# Encoders.net
KiCad netlist of a schematic drawn in Altium Designer
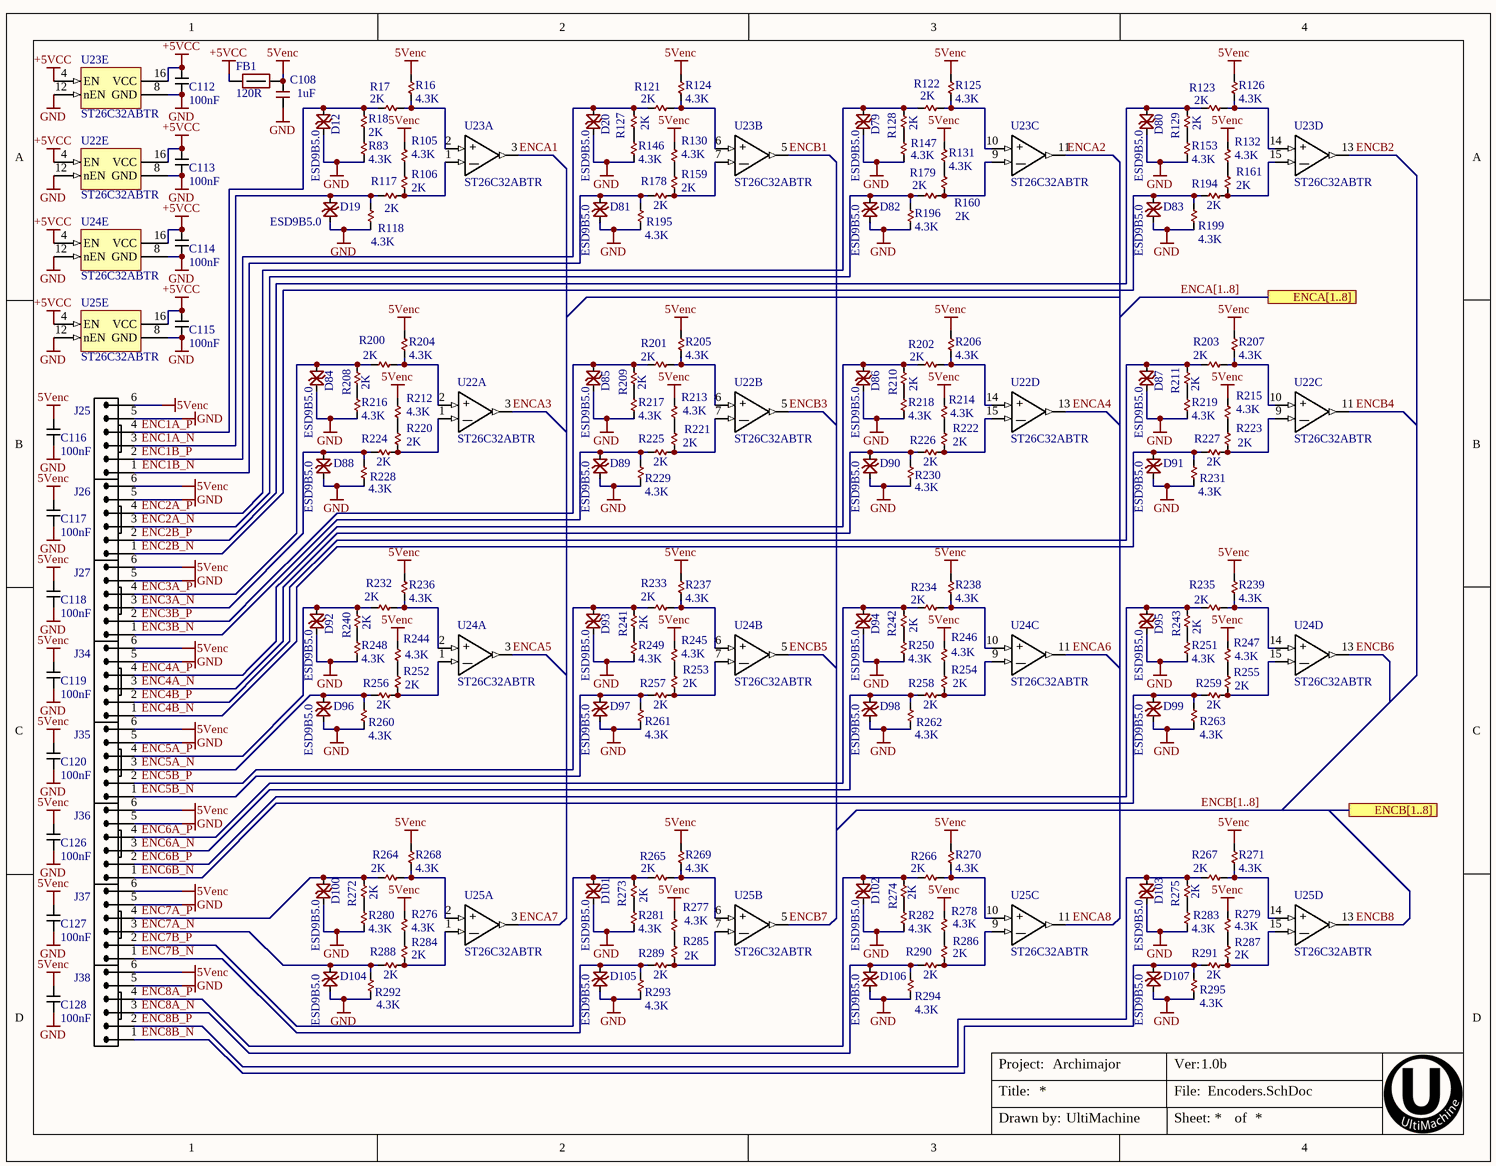
[diagram p0: Encoders.SchDoc]

(export (version "E")
  (design (tool "Eeschema 10.0.6"))
  (components
    (comp (ref "C108")
      (value "1uF")
      (footprint "C0402")
      (description "CAP CER 0402 1uF 6.3V 10% X5R")
      (fields (field (name "MANUFACTURER") "Murata") (field (name "PART") "1uF 6.3V X5R 0402"))
      (libsource (lib "Capacitors") (part "1uF 0402 6.3V X5R"))
    )
    (comp (ref "C112")
      (value "100nF")
      (footprint "C0201 Large Pads")
      (description "CAP CER 0.1UF 6.3V 10% X5R 0201")
      (fields (field (name "MANUFACTURER") "Samsung") (field (name "TOLERANCE") "10%"))
      (libsource (lib "Capacitors") (part "100nF 6.3V X5R 0201"))
    )
    (comp (ref "C113")
      (value "100nF")
      (footprint "C0201 Large Pads")
      (description "CAP CER 0.1UF 6.3V 10% X5R 0201")
      (fields (field (name "MANUFACTURER") "Samsung") (field (name "TOLERANCE") "10%"))
      (libsource (lib "Capacitors") (part "100nF 6.3V X5R 0201"))
    )
    (comp (ref "C114")
      (value "100nF")
      (footprint "C0201 Large Pads")
      (description "CAP CER 0.1UF 6.3V 10% X5R 0201")
      (fields (field (name "MANUFACTURER") "Samsung") (field (name "TOLERANCE") "10%"))
      (libsource (lib "Capacitors") (part "100nF 6.3V X5R 0201"))
    )
    (comp (ref "C115")
      (value "100nF")
      (footprint "C0201 Large Pads")
      (description "CAP CER 0.1UF 6.3V 10% X5R 0201")
      (fields (field (name "MANUFACTURER") "Samsung") (field (name "TOLERANCE") "10%"))
      (libsource (lib "Capacitors") (part "100nF 6.3V X5R 0201"))
    )
    (comp (ref "C116")
      (value "100nF")
      (footprint "C0201 Large Pads")
      (description "CAP CER 0.1UF 6.3V 10% X5R 0201")
      (fields (field (name "MANUFACTURER") "Samsung") (field (name "TOLERANCE") "10%"))
      (libsource (lib "Capacitors") (part "100nF 6.3V X5R 0201"))
    )
    (comp (ref "C117")
      (value "100nF")
      (footprint "C0201 Large Pads")
      (description "CAP CER 0.1UF 6.3V 10% X5R 0201")
      (fields (field (name "MANUFACTURER") "Samsung") (field (name "TOLERANCE") "10%"))
      (libsource (lib "Capacitors") (part "100nF 6.3V X5R 0201"))
    )
    (comp (ref "C118")
      (value "100nF")
      (footprint "C0201 Large Pads")
      (description "CAP CER 0.1UF 6.3V 10% X5R 0201")
      (fields (field (name "MANUFACTURER") "Samsung") (field (name "TOLERANCE") "10%"))
      (libsource (lib "Capacitors") (part "100nF 6.3V X5R 0201"))
    )
    (comp (ref "C119")
      (value "100nF")
      (footprint "C0201 Large Pads")
      (description "CAP CER 0.1UF 6.3V 10% X5R 0201")
      (fields (field (name "MANUFACTURER") "Samsung") (field (name "TOLERANCE") "10%"))
      (libsource (lib "Capacitors") (part "100nF 6.3V X5R 0201"))
    )
    (comp (ref "C120")
      (value "100nF")
      (footprint "C0201 Large Pads")
      (description "CAP CER 0.1UF 6.3V 10% X5R 0201")
      (fields (field (name "MANUFACTURER") "Samsung") (field (name "TOLERANCE") "10%"))
      (libsource (lib "Capacitors") (part "100nF 6.3V X5R 0201"))
    )
    (comp (ref "C126")
      (value "100nF")
      (footprint "C0201 Large Pads")
      (description "CAP CER 0.1UF 6.3V 10% X5R 0201")
      (fields (field (name "MANUFACTURER") "Samsung") (field (name "TOLERANCE") "10%"))
      (libsource (lib "Capacitors") (part "100nF 6.3V X5R 0201"))
    )
    (comp (ref "C127")
      (value "100nF")
      (footprint "C0201 Large Pads")
      (description "CAP CER 0.1UF 6.3V 10% X5R 0201")
      (fields (field (name "MANUFACTURER") "Samsung") (field (name "TOLERANCE") "10%"))
      (libsource (lib "Capacitors") (part "100nF 6.3V X5R 0201"))
    )
    (comp (ref "C128")
      (value "100nF")
      (footprint "C0201 Large Pads")
      (description "CAP CER 0.1UF 6.3V 10% X5R 0201")
      (fields (field (name "MANUFACTURER") "Samsung") (field (name "TOLERANCE") "10%"))
      (libsource (lib "Capacitors") (part "100nF 6.3V X5R 0201"))
    )
    (comp (ref "D12")
      (value "ESD9B5.0")
      (footprint "SOD923-D")
      (description "TVS DIODE BIDIR 5VWM SOD923")
      (fields (field (name "MANUFACTURER") "On Semi") (field (name "TOLERANCE") "-NA-"))
      (libsource (lib "Diodes") (part "ESD9B5.0ST5G"))
    )
    (comp (ref "D19")
      (value "ESD9B5.0")
      (footprint "SOD923-D")
      (description "TVS DIODE BIDIR 5VWM SOD923")
      (fields (field (name "MANUFACTURER") "On Semi") (field (name "TOLERANCE") "-NA-"))
      (libsource (lib "Diodes") (part "ESD9B5.0ST5G"))
    )
    (comp (ref "D20")
      (value "ESD9B5.0")
      (footprint "SOD923-D")
      (description "TVS DIODE BIDIR 5VWM SOD923")
      (fields (field (name "MANUFACTURER") "On Semi") (field (name "TOLERANCE") "-NA-"))
      (libsource (lib "Diodes") (part "ESD9B5.0ST5G"))
    )
    (comp (ref "D79")
      (value "ESD9B5.0")
      (footprint "SOD923-D")
      (description "TVS DIODE BIDIR 5VWM SOD923")
      (fields (field (name "MANUFACTURER") "On Semi") (field (name "TOLERANCE") "-NA-"))
      (libsource (lib "Diodes") (part "ESD9B5.0ST5G"))
    )
    (comp (ref "D80")
      (value "ESD9B5.0")
      (footprint "SOD923-D")
      (description "TVS DIODE BIDIR 5VWM SOD923")
      (fields (field (name "MANUFACTURER") "On Semi") (field (name "TOLERANCE") "-NA-"))
      (libsource (lib "Diodes") (part "ESD9B5.0ST5G"))
    )
    (comp (ref "D81")
      (value "ESD9B5.0")
      (footprint "SOD923-D")
      (description "TVS DIODE BIDIR 5VWM SOD923")
      (fields (field (name "MANUFACTURER") "On Semi") (field (name "TOLERANCE") "-NA-"))
      (libsource (lib "Diodes") (part "ESD9B5.0ST5G"))
    )
    (comp (ref "D82")
      (value "ESD9B5.0")
      (footprint "SOD923-D")
      (description "TVS DIODE BIDIR 5VWM SOD923")
      (fields (field (name "MANUFACTURER") "On Semi") (field (name "TOLERANCE") "-NA-"))
      (libsource (lib "Diodes") (part "ESD9B5.0ST5G"))
    )
    (comp (ref "D83")
      (value "ESD9B5.0")
      (footprint "SOD923-D")
      (description "TVS DIODE BIDIR 5VWM SOD923")
      (fields (field (name "MANUFACTURER") "On Semi") (field (name "TOLERANCE") "-NA-"))
      (libsource (lib "Diodes") (part "ESD9B5.0ST5G"))
    )
    (comp (ref "D84")
      (value "ESD9B5.0")
      (footprint "SOD923-D")
      (description "TVS DIODE BIDIR 5VWM SOD923")
      (fields (field (name "MANUFACTURER") "On Semi") (field (name "TOLERANCE") "-NA-"))
      (libsource (lib "Diodes") (part "ESD9B5.0ST5G"))
    )
    (comp (ref "D85")
      (value "ESD9B5.0")
      (footprint "SOD923-D")
      (description "TVS DIODE BIDIR 5VWM SOD923")
      (fields (field (name "MANUFACTURER") "On Semi") (field (name "TOLERANCE") "-NA-"))
      (libsource (lib "Diodes") (part "ESD9B5.0ST5G"))
    )
    (comp (ref "D86")
      (value "ESD9B5.0")
      (footprint "SOD923-D")
      (description "TVS DIODE BIDIR 5VWM SOD923")
      (fields (field (name "MANUFACTURER") "On Semi") (field (name "TOLERANCE") "-NA-"))
      (libsource (lib "Diodes") (part "ESD9B5.0ST5G"))
    )
    (comp (ref "D87")
      (value "ESD9B5.0")
      (footprint "SOD923-D")
      (description "TVS DIODE BIDIR 5VWM SOD923")
      (fields (field (name "MANUFACTURER") "On Semi") (field (name "TOLERANCE") "-NA-"))
      (libsource (lib "Diodes") (part "ESD9B5.0ST5G"))
    )
    (comp (ref "D88")
      (value "ESD9B5.0")
      (footprint "SOD923-D")
      (description "TVS DIODE BIDIR 5VWM SOD923")
      (fields (field (name "MANUFACTURER") "On Semi") (field (name "TOLERANCE") "-NA-"))
      (libsource (lib "Diodes") (part "ESD9B5.0ST5G"))
    )
    (comp (ref "D89")
      (value "ESD9B5.0")
      (footprint "SOD923-D")
      (description "TVS DIODE BIDIR 5VWM SOD923")
      (fields (field (name "MANUFACTURER") "On Semi") (field (name "TOLERANCE") "-NA-"))
      (libsource (lib "Diodes") (part "ESD9B5.0ST5G"))
    )
    (comp (ref "D90")
      (value "ESD9B5.0")
      (footprint "SOD923-D")
      (description "TVS DIODE BIDIR 5VWM SOD923")
      (fields (field (name "MANUFACTURER") "On Semi") (field (name "TOLERANCE") "-NA-"))
      (libsource (lib "Diodes") (part "ESD9B5.0ST5G"))
    )
    (comp (ref "D91")
      (value "ESD9B5.0")
      (footprint "SOD923-D")
      (description "TVS DIODE BIDIR 5VWM SOD923")
      (fields (field (name "MANUFACTURER") "On Semi") (field (name "TOLERANCE") "-NA-"))
      (libsource (lib "Diodes") (part "ESD9B5.0ST5G"))
    )
    (comp (ref "D92")
      (value "ESD9B5.0")
      (footprint "SOD923-D")
      (description "TVS DIODE BIDIR 5VWM SOD923")
      (fields (field (name "MANUFACTURER") "On Semi") (field (name "TOLERANCE") "-NA-"))
      (libsource (lib "Diodes") (part "ESD9B5.0ST5G"))
    )
    (comp (ref "D93")
      (value "ESD9B5.0")
      (footprint "SOD923-D")
      (description "TVS DIODE BIDIR 5VWM SOD923")
      (fields (field (name "MANUFACTURER") "On Semi") (field (name "TOLERANCE") "-NA-"))
      (libsource (lib "Diodes") (part "ESD9B5.0ST5G"))
    )
    (comp (ref "D94")
      (value "ESD9B5.0")
      (footprint "SOD923-D")
      (description "TVS DIODE BIDIR 5VWM SOD923")
      (fields (field (name "MANUFACTURER") "On Semi") (field (name "TOLERANCE") "-NA-"))
      (libsource (lib "Diodes") (part "ESD9B5.0ST5G"))
    )
    (comp (ref "D95")
      (value "ESD9B5.0")
      (footprint "SOD923-D")
      (description "TVS DIODE BIDIR 5VWM SOD923")
      (fields (field (name "MANUFACTURER") "On Semi") (field (name "TOLERANCE") "-NA-"))
      (libsource (lib "Diodes") (part "ESD9B5.0ST5G"))
    )
    (comp (ref "D96")
      (value "ESD9B5.0")
      (footprint "SOD923-D")
      (description "TVS DIODE BIDIR 5VWM SOD923")
      (fields (field (name "MANUFACTURER") "On Semi") (field (name "TOLERANCE") "-NA-"))
      (libsource (lib "Diodes") (part "ESD9B5.0ST5G"))
    )
    (comp (ref "D97")
      (value "ESD9B5.0")
      (footprint "SOD923-D")
      (description "TVS DIODE BIDIR 5VWM SOD923")
      (fields (field (name "MANUFACTURER") "On Semi") (field (name "TOLERANCE") "-NA-"))
      (libsource (lib "Diodes") (part "ESD9B5.0ST5G"))
    )
    (comp (ref "D98")
      (value "ESD9B5.0")
      (footprint "SOD923-D")
      (description "TVS DIODE BIDIR 5VWM SOD923")
      (fields (field (name "MANUFACTURER") "On Semi") (field (name "TOLERANCE") "-NA-"))
      (libsource (lib "Diodes") (part "ESD9B5.0ST5G"))
    )
    (comp (ref "D99")
      (value "ESD9B5.0")
      (footprint "SOD923-D")
      (description "TVS DIODE BIDIR 5VWM SOD923")
      (fields (field (name "MANUFACTURER") "On Semi") (field (name "TOLERANCE") "-NA-"))
      (libsource (lib "Diodes") (part "ESD9B5.0ST5G"))
    )
    (comp (ref "D100")
      (value "ESD9B5.0")
      (footprint "SOD923-D")
      (description "TVS DIODE BIDIR 5VWM SOD923")
      (fields (field (name "MANUFACTURER") "On Semi") (field (name "TOLERANCE") "-NA-"))
      (libsource (lib "Diodes") (part "ESD9B5.0ST5G"))
    )
    (comp (ref "D101")
      (value "ESD9B5.0")
      (footprint "SOD923-D")
      (description "TVS DIODE BIDIR 5VWM SOD923")
      (fields (field (name "MANUFACTURER") "On Semi") (field (name "TOLERANCE") "-NA-"))
      (libsource (lib "Diodes") (part "ESD9B5.0ST5G"))
    )
    (comp (ref "D102")
      (value "ESD9B5.0")
      (footprint "SOD923-D")
      (description "TVS DIODE BIDIR 5VWM SOD923")
      (fields (field (name "MANUFACTURER") "On Semi") (field (name "TOLERANCE") "-NA-"))
      (libsource (lib "Diodes") (part "ESD9B5.0ST5G"))
    )
    (comp (ref "D103")
      (value "ESD9B5.0")
      (footprint "SOD923-D")
      (description "TVS DIODE BIDIR 5VWM SOD923")
      (fields (field (name "MANUFACTURER") "On Semi") (field (name "TOLERANCE") "-NA-"))
      (libsource (lib "Diodes") (part "ESD9B5.0ST5G"))
    )
    (comp (ref "D104")
      (value "ESD9B5.0")
      (footprint "SOD923-D")
      (description "TVS DIODE BIDIR 5VWM SOD923")
      (fields (field (name "MANUFACTURER") "On Semi") (field (name "TOLERANCE") "-NA-"))
      (libsource (lib "Diodes") (part "ESD9B5.0ST5G"))
    )
    (comp (ref "D105")
      (value "ESD9B5.0")
      (footprint "SOD923-D")
      (description "TVS DIODE BIDIR 5VWM SOD923")
      (fields (field (name "MANUFACTURER") "On Semi") (field (name "TOLERANCE") "-NA-"))
      (libsource (lib "Diodes") (part "ESD9B5.0ST5G"))
    )
    (comp (ref "D106")
      (value "ESD9B5.0")
      (footprint "SOD923-D")
      (description "TVS DIODE BIDIR 5VWM SOD923")
      (fields (field (name "MANUFACTURER") "On Semi") (field (name "TOLERANCE") "-NA-"))
      (libsource (lib "Diodes") (part "ESD9B5.0ST5G"))
    )
    (comp (ref "D107")
      (value "ESD9B5.0")
      (footprint "SOD923-D")
      (description "TVS DIODE BIDIR 5VWM SOD923")
      (fields (field (name "MANUFACTURER") "On Semi") (field (name "TOLERANCE") "-NA-"))
      (libsource (lib "Diodes") (part "ESD9B5.0ST5G"))
    )
    (comp (ref "FB1")
      (value "120R")
      (footprint "FB0603")
      (description "FERRITE BEAD 120 OHM 0603 1LN")
      (fields (field (name "MANUFACTURER") "Samsung") (field (name "PART") "CIS10P121AC"))
      (libsource (lib "3Delight") (part "FERRITE 220R 2.5A 0603"))
    )
    (comp (ref "J25")
      (value "Molex 70543-05")
      (footprint "70543-05_PIN-IN-PASTE")
      (description "6 Positions Header, Shrouded Connector 0.100\" (2.54mm) Through Hole Gold - Pin in Paste")
      (fields (field (name "MANUFACTURER") "Molex") (field (name "PART") "6 Pin Conn VERT"))
      (libsource (lib "Connectors") (part "CONN 6POS VERT 0.1{dblquote} SHRD LOCKING PIP"))
    )
    (comp (ref "J26")
      (value "Molex 70543-05")
      (footprint "70543-05_PIN-IN-PASTE")
      (description "6 Positions Header, Shrouded Connector 0.100\" (2.54mm) Through Hole Gold - Pin in Paste")
      (fields (field (name "MANUFACTURER") "Molex") (field (name "PART") "6 Pin Conn VERT"))
      (libsource (lib "Connectors") (part "CONN 6POS VERT 0.1{dblquote} SHRD LOCKING PIP"))
    )
    (comp (ref "J27")
      (value "Molex 70543-05")
      (footprint "70543-05_PIN-IN-PASTE")
      (description "6 Positions Header, Shrouded Connector 0.100\" (2.54mm) Through Hole Gold - Pin in Paste")
      (fields (field (name "MANUFACTURER") "Molex") (field (name "PART") "6 Pin Conn VERT"))
      (libsource (lib "Connectors") (part "CONN 6POS VERT 0.1{dblquote} SHRD LOCKING PIP"))
    )
    (comp (ref "J34")
      (value "Molex 70543-05")
      (footprint "70543-05_PIN-IN-PASTE")
      (description "6 Positions Header, Shrouded Connector 0.100\" (2.54mm) Through Hole Gold - Pin in Paste")
      (fields (field (name "MANUFACTURER") "Molex") (field (name "PART") "6 Pin Conn VERT"))
      (libsource (lib "Connectors") (part "CONN 6POS VERT 0.1{dblquote} SHRD LOCKING PIP"))
    )
    (comp (ref "J35")
      (value "Molex 70543-05")
      (footprint "70543-05_PIN-IN-PASTE")
      (description "6 Positions Header, Shrouded Connector 0.100\" (2.54mm) Through Hole Gold - Pin in Paste")
      (fields (field (name "MANUFACTURER") "Molex") (field (name "PART") "6 Pin Conn VERT"))
      (libsource (lib "Connectors") (part "CONN 6POS VERT 0.1{dblquote} SHRD LOCKING PIP"))
    )
    (comp (ref "J36")
      (value "Molex 70543-05")
      (footprint "70543-05_PIN-IN-PASTE")
      (description "6 Positions Header, Shrouded Connector 0.100\" (2.54mm) Through Hole Gold - Pin in Paste")
      (fields (field (name "MANUFACTURER") "Molex") (field (name "PART") "6 Pin Conn VERT"))
      (libsource (lib "Connectors") (part "CONN 6POS VERT 0.1{dblquote} SHRD LOCKING PIP"))
    )
    (comp (ref "J37")
      (value "Molex 70543-05")
      (footprint "70543-05_PIN-IN-PASTE")
      (description "6 Positions Header, Shrouded Connector 0.100\" (2.54mm) Through Hole Gold - Pin in Paste")
      (fields (field (name "MANUFACTURER") "Molex") (field (name "PART") "6 Pin Conn VERT"))
      (libsource (lib "Connectors") (part "CONN 6POS VERT 0.1{dblquote} SHRD LOCKING PIP"))
    )
    (comp (ref "J38")
      (value "Molex 70543-05")
      (footprint "70543-05_PIN-IN-PASTE")
      (description "6 Positions Header, Shrouded Connector 0.100\" (2.54mm) Through Hole Gold - Pin in Paste")
      (fields (field (name "MANUFACTURER") "Molex") (field (name "PART") "6 Pin Conn VERT"))
      (libsource (lib "Connectors") (part "CONN 6POS VERT 0.1{dblquote} SHRD LOCKING PIP"))
    )
    (comp (ref "R16")
      (value "4.3K")
      (footprint "R0402")
      (description "RES SMD 4.3K OHM 1% 1/16W 0402")
      (fields (field (name "MANUFACTURER") "Yageo") (field (name "PART") "4.3K 1% 0402"))
      (libsource (lib "Resistors") (part "4.3K 1% 0402"))
    )
    (comp (ref "R17")
      (value "2K")
      (footprint "R0402")
      (description "RES SMD 2K OHM 1% 1/16W 0402")
      (fields (field (name "MANUFACTURER") "Yageo") (field (name "PART") "2k 1% 0402"))
      (libsource (lib "Resistors") (part "2K 1% 0402"))
    )
    (comp (ref "R18")
      (value "2K")
      (footprint "R0402")
      (description "RES SMD 2K OHM 1% 1/16W 0402")
      (fields (field (name "MANUFACTURER") "Yageo") (field (name "PART") "2k 1% 0402"))
      (libsource (lib "Resistors") (part "2K 1% 0402"))
    )
    (comp (ref "R83")
      (value "4.3K")
      (footprint "R0402")
      (description "RES SMD 4.3K OHM 1% 1/16W 0402")
      (fields (field (name "MANUFACTURER") "Yageo") (field (name "PART") "4.3K 1% 0402"))
      (libsource (lib "Resistors") (part "4.3K 1% 0402"))
    )
    (comp (ref "R105")
      (value "4.3K")
      (footprint "R0402")
      (description "RES SMD 4.3K OHM 1% 1/16W 0402")
      (fields (field (name "MANUFACTURER") "Yageo") (field (name "PART") "4.3K 1% 0402"))
      (libsource (lib "Resistors") (part "4.3K 1% 0402"))
    )
    (comp (ref "R106")
      (value "2K")
      (footprint "R0402")
      (description "RES SMD 2K OHM 1% 1/16W 0402")
      (fields (field (name "MANUFACTURER") "Yageo") (field (name "PART") "2k 1% 0402"))
      (libsource (lib "Resistors") (part "2K 1% 0402"))
    )
    (comp (ref "R117")
      (value "2K")
      (footprint "R0402")
      (description "RES SMD 2K OHM 1% 1/16W 0402")
      (fields (field (name "MANUFACTURER") "Yageo") (field (name "PART") "2k 1% 0402"))
      (libsource (lib "Resistors") (part "2K 1% 0402"))
    )
    (comp (ref "R118")
      (value "4.3K")
      (footprint "R0402")
      (description "RES SMD 4.3K OHM 1% 1/16W 0402")
      (fields (field (name "MANUFACTURER") "Yageo") (field (name "PART") "4.3K 1% 0402"))
      (libsource (lib "Resistors") (part "4.3K 1% 0402"))
    )
    (comp (ref "R121")
      (value "2K")
      (footprint "R0402")
      (description "RES SMD 2K OHM 1% 1/16W 0402")
      (fields (field (name "MANUFACTURER") "Yageo") (field (name "PART") "2k 1% 0402"))
      (libsource (lib "Resistors") (part "2K 1% 0402"))
    )
    (comp (ref "R122")
      (value "2K")
      (footprint "R0402")
      (description "RES SMD 2K OHM 1% 1/16W 0402")
      (fields (field (name "MANUFACTURER") "Yageo") (field (name "PART") "2k 1% 0402"))
      (libsource (lib "Resistors") (part "2K 1% 0402"))
    )
    (comp (ref "R123")
      (value "2K")
      (footprint "R0402")
      (description "RES SMD 2K OHM 1% 1/16W 0402")
      (fields (field (name "MANUFACTURER") "Yageo") (field (name "PART") "2k 1% 0402"))
      (libsource (lib "Resistors") (part "2K 1% 0402"))
    )
    (comp (ref "R124")
      (value "4.3K")
      (footprint "R0402")
      (description "RES SMD 4.3K OHM 1% 1/16W 0402")
      (fields (field (name "MANUFACTURER") "Yageo") (field (name "PART") "4.3K 1% 0402"))
      (libsource (lib "Resistors") (part "4.3K 1% 0402"))
    )
    (comp (ref "R125")
      (value "4.3K")
      (footprint "R0402")
      (description "RES SMD 4.3K OHM 1% 1/16W 0402")
      (fields (field (name "MANUFACTURER") "Yageo") (field (name "PART") "4.3K 1% 0402"))
      (libsource (lib "Resistors") (part "4.3K 1% 0402"))
    )
    (comp (ref "R126")
      (value "4.3K")
      (footprint "R0402")
      (description "RES SMD 4.3K OHM 1% 1/16W 0402")
      (fields (field (name "MANUFACTURER") "Yageo") (field (name "PART") "4.3K 1% 0402"))
      (libsource (lib "Resistors") (part "4.3K 1% 0402"))
    )
    (comp (ref "R127")
      (value "2K")
      (footprint "R0402")
      (description "RES SMD 2K OHM 1% 1/16W 0402")
      (fields (field (name "MANUFACTURER") "Yageo") (field (name "PART") "2k 1% 0402"))
      (libsource (lib "Resistors") (part "2K 1% 0402"))
    )
    (comp (ref "R128")
      (value "2K")
      (footprint "R0402")
      (description "RES SMD 2K OHM 1% 1/16W 0402")
      (fields (field (name "MANUFACTURER") "Yageo") (field (name "PART") "2k 1% 0402"))
      (libsource (lib "Resistors") (part "2K 1% 0402"))
    )
    (comp (ref "R129")
      (value "2K")
      (footprint "R0402")
      (description "RES SMD 2K OHM 1% 1/16W 0402")
      (fields (field (name "MANUFACTURER") "Yageo") (field (name "PART") "2k 1% 0402"))
      (libsource (lib "Resistors") (part "2K 1% 0402"))
    )
    (comp (ref "R130")
      (value "4.3K")
      (footprint "R0402")
      (description "RES SMD 4.3K OHM 1% 1/16W 0402")
      (fields (field (name "MANUFACTURER") "Yageo") (field (name "PART") "4.3K 1% 0402"))
      (libsource (lib "Resistors") (part "4.3K 1% 0402"))
    )
    (comp (ref "R131")
      (value "4.3K")
      (footprint "R0402")
      (description "RES SMD 4.3K OHM 1% 1/16W 0402")
      (fields (field (name "MANUFACTURER") "Yageo") (field (name "PART") "4.3K 1% 0402"))
      (libsource (lib "Resistors") (part "4.3K 1% 0402"))
    )
    (comp (ref "R132")
      (value "4.3K")
      (footprint "R0402")
      (description "RES SMD 4.3K OHM 1% 1/16W 0402")
      (fields (field (name "MANUFACTURER") "Yageo") (field (name "PART") "4.3K 1% 0402"))
      (libsource (lib "Resistors") (part "4.3K 1% 0402"))
    )
    (comp (ref "R146")
      (value "4.3K")
      (footprint "R0402")
      (description "RES SMD 4.3K OHM 1% 1/16W 0402")
      (fields (field (name "MANUFACTURER") "Yageo") (field (name "PART") "4.3K 1% 0402"))
      (libsource (lib "Resistors") (part "4.3K 1% 0402"))
    )
    (comp (ref "R147")
      (value "4.3K")
      (footprint "R0402")
      (description "RES SMD 4.3K OHM 1% 1/16W 0402")
      (fields (field (name "MANUFACTURER") "Yageo") (field (name "PART") "4.3K 1% 0402"))
      (libsource (lib "Resistors") (part "4.3K 1% 0402"))
    )
    (comp (ref "R153")
      (value "4.3K")
      (footprint "R0402")
      (description "RES SMD 4.3K OHM 1% 1/16W 0402")
      (fields (field (name "MANUFACTURER") "Yageo") (field (name "PART") "4.3K 1% 0402"))
      (libsource (lib "Resistors") (part "4.3K 1% 0402"))
    )
    (comp (ref "R159")
      (value "2K")
      (footprint "R0402")
      (description "RES SMD 2K OHM 1% 1/16W 0402")
      (fields (field (name "MANUFACTURER") "Yageo") (field (name "PART") "2k 1% 0402"))
      (libsource (lib "Resistors") (part "2K 1% 0402"))
    )
    (comp (ref "R160")
      (value "2K")
      (footprint "R0402")
      (description "RES SMD 2K OHM 1% 1/16W 0402")
      (fields (field (name "MANUFACTURER") "Yageo") (field (name "PART") "2k 1% 0402"))
      (libsource (lib "Resistors") (part "2K 1% 0402"))
    )
    (comp (ref "R161")
      (value "2K")
      (footprint "R0402")
      (description "RES SMD 2K OHM 1% 1/16W 0402")
      (fields (field (name "MANUFACTURER") "Yageo") (field (name "PART") "2k 1% 0402"))
      (libsource (lib "Resistors") (part "2K 1% 0402"))
    )
    (comp (ref "R178")
      (value "2K")
      (footprint "R0402")
      (description "RES SMD 2K OHM 1% 1/16W 0402")
      (fields (field (name "MANUFACTURER") "Yageo") (field (name "PART") "2k 1% 0402"))
      (libsource (lib "Resistors") (part "2K 1% 0402"))
    )
    (comp (ref "R179")
      (value "2K")
      (footprint "R0402")
      (description "RES SMD 2K OHM 1% 1/16W 0402")
      (fields (field (name "MANUFACTURER") "Yageo") (field (name "PART") "2k 1% 0402"))
      (libsource (lib "Resistors") (part "2K 1% 0402"))
    )
    (comp (ref "R194")
      (value "2K")
      (footprint "R0402")
      (description "RES SMD 2K OHM 1% 1/16W 0402")
      (fields (field (name "MANUFACTURER") "Yageo") (field (name "PART") "2k 1% 0402"))
      (libsource (lib "Resistors") (part "2K 1% 0402"))
    )
    (comp (ref "R195")
      (value "4.3K")
      (footprint "R0402")
      (description "RES SMD 4.3K OHM 1% 1/16W 0402")
      (fields (field (name "MANUFACTURER") "Yageo") (field (name "PART") "4.3K 1% 0402"))
      (libsource (lib "Resistors") (part "4.3K 1% 0402"))
    )
    (comp (ref "R196")
      (value "4.3K")
      (footprint "R0402")
      (description "RES SMD 4.3K OHM 1% 1/16W 0402")
      (fields (field (name "MANUFACTURER") "Yageo") (field (name "PART") "4.3K 1% 0402"))
      (libsource (lib "Resistors") (part "4.3K 1% 0402"))
    )
    (comp (ref "R199")
      (value "4.3K")
      (footprint "R0402")
      (description "RES SMD 4.3K OHM 1% 1/16W 0402")
      (fields (field (name "MANUFACTURER") "Yageo") (field (name "PART") "4.3K 1% 0402"))
      (libsource (lib "Resistors") (part "4.3K 1% 0402"))
    )
    (comp (ref "R200")
      (value "2K")
      (footprint "R0402")
      (description "RES SMD 2K OHM 1% 1/16W 0402")
      (fields (field (name "MANUFACTURER") "Yageo") (field (name "PART") "2k 1% 0402"))
      (libsource (lib "Resistors") (part "2K 1% 0402"))
    )
    (comp (ref "R201")
      (value "2K")
      (footprint "R0402")
      (description "RES SMD 2K OHM 1% 1/16W 0402")
      (fields (field (name "MANUFACTURER") "Yageo") (field (name "PART") "2k 1% 0402"))
      (libsource (lib "Resistors") (part "2K 1% 0402"))
    )
    (comp (ref "R202")
      (value "2K")
      (footprint "R0402")
      (description "RES SMD 2K OHM 1% 1/16W 0402")
      (fields (field (name "MANUFACTURER") "Yageo") (field (name "PART") "2k 1% 0402"))
      (libsource (lib "Resistors") (part "2K 1% 0402"))
    )
    (comp (ref "R203")
      (value "2K")
      (footprint "R0402")
      (description "RES SMD 2K OHM 1% 1/16W 0402")
      (fields (field (name "MANUFACTURER") "Yageo") (field (name "PART") "2k 1% 0402"))
      (libsource (lib "Resistors") (part "2K 1% 0402"))
    )
    (comp (ref "R204")
      (value "4.3K")
      (footprint "R0402")
      (description "RES SMD 4.3K OHM 1% 1/16W 0402")
      (fields (field (name "MANUFACTURER") "Yageo") (field (name "PART") "4.3K 1% 0402"))
      (libsource (lib "Resistors") (part "4.3K 1% 0402"))
    )
    (comp (ref "R205")
      (value "4.3K")
      (footprint "R0402")
      (description "RES SMD 4.3K OHM 1% 1/16W 0402")
      (fields (field (name "MANUFACTURER") "Yageo") (field (name "PART") "4.3K 1% 0402"))
      (libsource (lib "Resistors") (part "4.3K 1% 0402"))
    )
    (comp (ref "R206")
      (value "4.3K")
      (footprint "R0402")
      (description "RES SMD 4.3K OHM 1% 1/16W 0402")
      (fields (field (name "MANUFACTURER") "Yageo") (field (name "PART") "4.3K 1% 0402"))
      (libsource (lib "Resistors") (part "4.3K 1% 0402"))
    )
    (comp (ref "R207")
      (value "4.3K")
      (footprint "R0402")
      (description "RES SMD 4.3K OHM 1% 1/16W 0402")
      (fields (field (name "MANUFACTURER") "Yageo") (field (name "PART") "4.3K 1% 0402"))
      (libsource (lib "Resistors") (part "4.3K 1% 0402"))
    )
    (comp (ref "R208")
      (value "2K")
      (footprint "R0402")
      (description "RES SMD 2K OHM 1% 1/16W 0402")
      (fields (field (name "MANUFACTURER") "Yageo") (field (name "PART") "2k 1% 0402"))
      (libsource (lib "Resistors") (part "2K 1% 0402"))
    )
    (comp (ref "R209")
      (value "2K")
      (footprint "R0402")
      (description "RES SMD 2K OHM 1% 1/16W 0402")
      (fields (field (name "MANUFACTURER") "Yageo") (field (name "PART") "2k 1% 0402"))
      (libsource (lib "Resistors") (part "2K 1% 0402"))
    )
    (comp (ref "R210")
      (value "2K")
      (footprint "R0402")
      (description "RES SMD 2K OHM 1% 1/16W 0402")
      (fields (field (name "MANUFACTURER") "Yageo") (field (name "PART") "2k 1% 0402"))
      (libsource (lib "Resistors") (part "2K 1% 0402"))
    )
    (comp (ref "R211")
      (value "2K")
      (footprint "R0402")
      (description "RES SMD 2K OHM 1% 1/16W 0402")
      (fields (field (name "MANUFACTURER") "Yageo") (field (name "PART") "2k 1% 0402"))
      (libsource (lib "Resistors") (part "2K 1% 0402"))
    )
    (comp (ref "R212")
      (value "4.3K")
      (footprint "R0402")
      (description "RES SMD 4.3K OHM 1% 1/16W 0402")
      (fields (field (name "MANUFACTURER") "Yageo") (field (name "PART") "4.3K 1% 0402"))
      (libsource (lib "Resistors") (part "4.3K 1% 0402"))
    )
    (comp (ref "R213")
      (value "4.3K")
      (footprint "R0402")
      (description "RES SMD 4.3K OHM 1% 1/16W 0402")
      (fields (field (name "MANUFACTURER") "Yageo") (field (name "PART") "4.3K 1% 0402"))
      (libsource (lib "Resistors") (part "4.3K 1% 0402"))
    )
    (comp (ref "R214")
      (value "4.3K")
      (footprint "R0402")
      (description "RES SMD 4.3K OHM 1% 1/16W 0402")
      (fields (field (name "MANUFACTURER") "Yageo") (field (name "PART") "4.3K 1% 0402"))
      (libsource (lib "Resistors") (part "4.3K 1% 0402"))
    )
    (comp (ref "R215")
      (value "4.3K")
      (footprint "R0402")
      (description "RES SMD 4.3K OHM 1% 1/16W 0402")
      (fields (field (name "MANUFACTURER") "Yageo") (field (name "PART") "4.3K 1% 0402"))
      (libsource (lib "Resistors") (part "4.3K 1% 0402"))
    )
    (comp (ref "R216")
      (value "4.3K")
      (footprint "R0402")
      (description "RES SMD 4.3K OHM 1% 1/16W 0402")
      (fields (field (name "MANUFACTURER") "Yageo") (field (name "PART") "4.3K 1% 0402"))
      (libsource (lib "Resistors") (part "4.3K 1% 0402"))
    )
    (comp (ref "R217")
      (value "4.3K")
      (footprint "R0402")
      (description "RES SMD 4.3K OHM 1% 1/16W 0402")
      (fields (field (name "MANUFACTURER") "Yageo") (field (name "PART") "4.3K 1% 0402"))
      (libsource (lib "Resistors") (part "4.3K 1% 0402"))
    )
    (comp (ref "R218")
      (value "4.3K")
      (footprint "R0402")
      (description "RES SMD 4.3K OHM 1% 1/16W 0402")
      (fields (field (name "MANUFACTURER") "Yageo") (field (name "PART") "4.3K 1% 0402"))
      (libsource (lib "Resistors") (part "4.3K 1% 0402"))
    )
    (comp (ref "R219")
      (value "4.3K")
      (footprint "R0402")
      (description "RES SMD 4.3K OHM 1% 1/16W 0402")
      (fields (field (name "MANUFACTURER") "Yageo") (field (name "PART") "4.3K 1% 0402"))
      (libsource (lib "Resistors") (part "4.3K 1% 0402"))
    )
    (comp (ref "R220")
      (value "2K")
      (footprint "R0402")
      (description "RES SMD 2K OHM 1% 1/16W 0402")
      (fields (field (name "MANUFACTURER") "Yageo") (field (name "PART") "2k 1% 0402"))
      (libsource (lib "Resistors") (part "2K 1% 0402"))
    )
    (comp (ref "R221")
      (value "2K")
      (footprint "R0402")
      (description "RES SMD 2K OHM 1% 1/16W 0402")
      (fields (field (name "MANUFACTURER") "Yageo") (field (name "PART") "2k 1% 0402"))
      (libsource (lib "Resistors") (part "2K 1% 0402"))
    )
    (comp (ref "R222")
      (value "2K")
      (footprint "R0402")
      (description "RES SMD 2K OHM 1% 1/16W 0402")
      (fields (field (name "MANUFACTURER") "Yageo") (field (name "PART") "2k 1% 0402"))
      (libsource (lib "Resistors") (part "2K 1% 0402"))
    )
    (comp (ref "R223")
      (value "2K")
      (footprint "R0402")
      (description "RES SMD 2K OHM 1% 1/16W 0402")
      (fields (field (name "MANUFACTURER") "Yageo") (field (name "PART") "2k 1% 0402"))
      (libsource (lib "Resistors") (part "2K 1% 0402"))
    )
    (comp (ref "R224")
      (value "2K")
      (footprint "R0402")
      (description "RES SMD 2K OHM 1% 1/16W 0402")
      (fields (field (name "MANUFACTURER") "Yageo") (field (name "PART") "2k 1% 0402"))
      (libsource (lib "Resistors") (part "2K 1% 0402"))
    )
    (comp (ref "R225")
      (value "2K")
      (footprint "R0402")
      (description "RES SMD 2K OHM 1% 1/16W 0402")
      (fields (field (name "MANUFACTURER") "Yageo") (field (name "PART") "2k 1% 0402"))
      (libsource (lib "Resistors") (part "2K 1% 0402"))
    )
    (comp (ref "R226")
      (value "2K")
      (footprint "R0402")
      (description "RES SMD 2K OHM 1% 1/16W 0402")
      (fields (field (name "MANUFACTURER") "Yageo") (field (name "PART") "2k 1% 0402"))
      (libsource (lib "Resistors") (part "2K 1% 0402"))
    )
    (comp (ref "R227")
      (value "2K")
      (footprint "R0402")
      (description "RES SMD 2K OHM 1% 1/16W 0402")
      (fields (field (name "MANUFACTURER") "Yageo") (field (name "PART") "2k 1% 0402"))
      (libsource (lib "Resistors") (part "2K 1% 0402"))
    )
    (comp (ref "R228")
      (value "4.3K")
      (footprint "R0402")
      (description "RES SMD 4.3K OHM 1% 1/16W 0402")
      (fields (field (name "MANUFACTURER") "Yageo") (field (name "PART") "4.3K 1% 0402"))
      (libsource (lib "Resistors") (part "4.3K 1% 0402"))
    )
    (comp (ref "R229")
      (value "4.3K")
      (footprint "R0402")
      (description "RES SMD 4.3K OHM 1% 1/16W 0402")
      (fields (field (name "MANUFACTURER") "Yageo") (field (name "PART") "4.3K 1% 0402"))
      (libsource (lib "Resistors") (part "4.3K 1% 0402"))
    )
    (comp (ref "R230")
      (value "4.3K")
      (footprint "R0402")
      (description "RES SMD 4.3K OHM 1% 1/16W 0402")
      (fields (field (name "MANUFACTURER") "Yageo") (field (name "PART") "4.3K 1% 0402"))
      (libsource (lib "Resistors") (part "4.3K 1% 0402"))
    )
    (comp (ref "R231")
      (value "4.3K")
      (footprint "R0402")
      (description "RES SMD 4.3K OHM 1% 1/16W 0402")
      (fields (field (name "MANUFACTURER") "Yageo") (field (name "PART") "4.3K 1% 0402"))
      (libsource (lib "Resistors") (part "4.3K 1% 0402"))
    )
    (comp (ref "R232")
      (value "2K")
      (footprint "R0402")
      (description "RES SMD 2K OHM 1% 1/16W 0402")
      (fields (field (name "MANUFACTURER") "Yageo") (field (name "PART") "2k 1% 0402"))
      (libsource (lib "Resistors") (part "2K 1% 0402"))
    )
    (comp (ref "R233")
      (value "2K")
      (footprint "R0402")
      (description "RES SMD 2K OHM 1% 1/16W 0402")
      (fields (field (name "MANUFACTURER") "Yageo") (field (name "PART") "2k 1% 0402"))
      (libsource (lib "Resistors") (part "2K 1% 0402"))
    )
    (comp (ref "R234")
      (value "2K")
      (footprint "R0402")
      (description "RES SMD 2K OHM 1% 1/16W 0402")
      (fields (field (name "MANUFACTURER") "Yageo") (field (name "PART") "2k 1% 0402"))
      (libsource (lib "Resistors") (part "2K 1% 0402"))
    )
    (comp (ref "R235")
      (value "2K")
      (footprint "R0402")
      (description "RES SMD 2K OHM 1% 1/16W 0402")
      (fields (field (name "MANUFACTURER") "Yageo") (field (name "PART") "2k 1% 0402"))
      (libsource (lib "Resistors") (part "2K 1% 0402"))
    )
    (comp (ref "R236")
      (value "4.3K")
      (footprint "R0402")
      (description "RES SMD 4.3K OHM 1% 1/16W 0402")
      (fields (field (name "MANUFACTURER") "Yageo") (field (name "PART") "4.3K 1% 0402"))
      (libsource (lib "Resistors") (part "4.3K 1% 0402"))
    )
    (comp (ref "R237")
      (value "4.3K")
      (footprint "R0402")
      (description "RES SMD 4.3K OHM 1% 1/16W 0402")
      (fields (field (name "MANUFACTURER") "Yageo") (field (name "PART") "4.3K 1% 0402"))
      (libsource (lib "Resistors") (part "4.3K 1% 0402"))
    )
    (comp (ref "R238")
      (value "4.3K")
      (footprint "R0402")
      (description "RES SMD 4.3K OHM 1% 1/16W 0402")
      (fields (field (name "MANUFACTURER") "Yageo") (field (name "PART") "4.3K 1% 0402"))
      (libsource (lib "Resistors") (part "4.3K 1% 0402"))
    )
    (comp (ref "R239")
      (value "4.3K")
      (footprint "R0402")
      (description "RES SMD 4.3K OHM 1% 1/16W 0402")
      (fields (field (name "MANUFACTURER") "Yageo") (field (name "PART") "4.3K 1% 0402"))
      (libsource (lib "Resistors") (part "4.3K 1% 0402"))
    )
    (comp (ref "R240")
      (value "2K")
      (footprint "R0402")
      (description "RES SMD 2K OHM 1% 1/16W 0402")
      (fields (field (name "MANUFACTURER") "Yageo") (field (name "PART") "2k 1% 0402"))
      (libsource (lib "Resistors") (part "2K 1% 0402"))
    )
    (comp (ref "R241")
      (value "2K")
      (footprint "R0402")
      (description "RES SMD 2K OHM 1% 1/16W 0402")
      (fields (field (name "MANUFACTURER") "Yageo") (field (name "PART") "2k 1% 0402"))
      (libsource (lib "Resistors") (part "2K 1% 0402"))
    )
    (comp (ref "R242")
      (value "2K")
      (footprint "R0402")
      (description "RES SMD 2K OHM 1% 1/16W 0402")
      (fields (field (name "MANUFACTURER") "Yageo") (field (name "PART") "2k 1% 0402"))
      (libsource (lib "Resistors") (part "2K 1% 0402"))
    )
    (comp (ref "R243")
      (value "2K")
      (footprint "R0402")
      (description "RES SMD 2K OHM 1% 1/16W 0402")
      (fields (field (name "MANUFACTURER") "Yageo") (field (name "PART") "2k 1% 0402"))
      (libsource (lib "Resistors") (part "2K 1% 0402"))
    )
    (comp (ref "R244")
      (value "4.3K")
      (footprint "R0402")
      (description "RES SMD 4.3K OHM 1% 1/16W 0402")
      (fields (field (name "MANUFACTURER") "Yageo") (field (name "PART") "4.3K 1% 0402"))
      (libsource (lib "Resistors") (part "4.3K 1% 0402"))
    )
    (comp (ref "R245")
      (value "4.3K")
      (footprint "R0402")
      (description "RES SMD 4.3K OHM 1% 1/16W 0402")
      (fields (field (name "MANUFACTURER") "Yageo") (field (name "PART") "4.3K 1% 0402"))
      (libsource (lib "Resistors") (part "4.3K 1% 0402"))
    )
    (comp (ref "R246")
      (value "4.3K")
      (footprint "R0402")
      (description "RES SMD 4.3K OHM 1% 1/16W 0402")
      (fields (field (name "MANUFACTURER") "Yageo") (field (name "PART") "4.3K 1% 0402"))
      (libsource (lib "Resistors") (part "4.3K 1% 0402"))
    )
    (comp (ref "R247")
      (value "4.3K")
      (footprint "R0402")
      (description "RES SMD 4.3K OHM 1% 1/16W 0402")
      (fields (field (name "MANUFACTURER") "Yageo") (field (name "PART") "4.3K 1% 0402"))
      (libsource (lib "Resistors") (part "4.3K 1% 0402"))
    )
    (comp (ref "R248")
      (value "4.3K")
      (footprint "R0402")
      (description "RES SMD 4.3K OHM 1% 1/16W 0402")
      (fields (field (name "MANUFACTURER") "Yageo") (field (name "PART") "4.3K 1% 0402"))
      (libsource (lib "Resistors") (part "4.3K 1% 0402"))
    )
    (comp (ref "R249")
      (value "4.3K")
      (footprint "R0402")
      (description "RES SMD 4.3K OHM 1% 1/16W 0402")
      (fields (field (name "MANUFACTURER") "Yageo") (field (name "PART") "4.3K 1% 0402"))
      (libsource (lib "Resistors") (part "4.3K 1% 0402"))
    )
    (comp (ref "R250")
      (value "4.3K")
      (footprint "R0402")
      (description "RES SMD 4.3K OHM 1% 1/16W 0402")
      (fields (field (name "MANUFACTURER") "Yageo") (field (name "PART") "4.3K 1% 0402"))
      (libsource (lib "Resistors") (part "4.3K 1% 0402"))
    )
    (comp (ref "R251")
      (value "4.3K")
      (footprint "R0402")
      (description "RES SMD 4.3K OHM 1% 1/16W 0402")
      (fields (field (name "MANUFACTURER") "Yageo") (field (name "PART") "4.3K 1% 0402"))
      (libsource (lib "Resistors") (part "4.3K 1% 0402"))
    )
    (comp (ref "R252")
      (value "2K")
      (footprint "R0402")
      (description "RES SMD 2K OHM 1% 1/16W 0402")
      (fields (field (name "MANUFACTURER") "Yageo") (field (name "PART") "2k 1% 0402"))
      (libsource (lib "Resistors") (part "2K 1% 0402"))
    )
    (comp (ref "R253")
      (value "2K")
      (footprint "R0402")
      (description "RES SMD 2K OHM 1% 1/16W 0402")
      (fields (field (name "MANUFACTURER") "Yageo") (field (name "PART") "2k 1% 0402"))
      (libsource (lib "Resistors") (part "2K 1% 0402"))
    )
    (comp (ref "R254")
      (value "2K")
      (footprint "R0402")
      (description "RES SMD 2K OHM 1% 1/16W 0402")
      (fields (field (name "MANUFACTURER") "Yageo") (field (name "PART") "2k 1% 0402"))
      (libsource (lib "Resistors") (part "2K 1% 0402"))
    )
    (comp (ref "R255")
      (value "2K")
      (footprint "R0402")
      (description "RES SMD 2K OHM 1% 1/16W 0402")
      (fields (field (name "MANUFACTURER") "Yageo") (field (name "PART") "2k 1% 0402"))
      (libsource (lib "Resistors") (part "2K 1% 0402"))
    )
    (comp (ref "R256")
      (value "2K")
      (footprint "R0402")
      (description "RES SMD 2K OHM 1% 1/16W 0402")
      (fields (field (name "MANUFACTURER") "Yageo") (field (name "PART") "2k 1% 0402"))
      (libsource (lib "Resistors") (part "2K 1% 0402"))
    )
    (comp (ref "R257")
      (value "2K")
      (footprint "R0402")
      (description "RES SMD 2K OHM 1% 1/16W 0402")
      (fields (field (name "MANUFACTURER") "Yageo") (field (name "PART") "2k 1% 0402"))
      (libsource (lib "Resistors") (part "2K 1% 0402"))
    )
    (comp (ref "R258")
      (value "2K")
      (footprint "R0402")
      (description "RES SMD 2K OHM 1% 1/16W 0402")
      (fields (field (name "MANUFACTURER") "Yageo") (field (name "PART") "2k 1% 0402"))
      (libsource (lib "Resistors") (part "2K 1% 0402"))
    )
    (comp (ref "R259")
      (value "2K")
      (footprint "R0402")
      (description "RES SMD 2K OHM 1% 1/16W 0402")
      (fields (field (name "MANUFACTURER") "Yageo") (field (name "PART") "2k 1% 0402"))
      (libsource (lib "Resistors") (part "2K 1% 0402"))
    )
    (comp (ref "R260")
      (value "4.3K")
      (footprint "R0402")
      (description "RES SMD 4.3K OHM 1% 1/16W 0402")
      (fields (field (name "MANUFACTURER") "Yageo") (field (name "PART") "4.3K 1% 0402"))
      (libsource (lib "Resistors") (part "4.3K 1% 0402"))
    )
    (comp (ref "R261")
      (value "4.3K")
      (footprint "R0402")
      (description "RES SMD 4.3K OHM 1% 1/16W 0402")
      (fields (field (name "MANUFACTURER") "Yageo") (field (name "PART") "4.3K 1% 0402"))
      (libsource (lib "Resistors") (part "4.3K 1% 0402"))
    )
    (comp (ref "R262")
      (value "4.3K")
      (footprint "R0402")
      (description "RES SMD 4.3K OHM 1% 1/16W 0402")
      (fields (field (name "MANUFACTURER") "Yageo") (field (name "PART") "4.3K 1% 0402"))
      (libsource (lib "Resistors") (part "4.3K 1% 0402"))
    )
    (comp (ref "R263")
      (value "4.3K")
      (footprint "R0402")
      (description "RES SMD 4.3K OHM 1% 1/16W 0402")
      (fields (field (name "MANUFACTURER") "Yageo") (field (name "PART") "4.3K 1% 0402"))
      (libsource (lib "Resistors") (part "4.3K 1% 0402"))
    )
    (comp (ref "R264")
      (value "2K")
      (footprint "R0402")
      (description "RES SMD 2K OHM 1% 1/16W 0402")
      (fields (field (name "MANUFACTURER") "Yageo") (field (name "PART") "2k 1% 0402"))
      (libsource (lib "Resistors") (part "2K 1% 0402"))
    )
    (comp (ref "R265")
      (value "2K")
      (footprint "R0402")
      (description "RES SMD 2K OHM 1% 1/16W 0402")
      (fields (field (name "MANUFACTURER") "Yageo") (field (name "PART") "2k 1% 0402"))
      (libsource (lib "Resistors") (part "2K 1% 0402"))
    )
    (comp (ref "R266")
      (value "2K")
      (footprint "R0402")
      (description "RES SMD 2K OHM 1% 1/16W 0402")
      (fields (field (name "MANUFACTURER") "Yageo") (field (name "PART") "2k 1% 0402"))
      (libsource (lib "Resistors") (part "2K 1% 0402"))
    )
    (comp (ref "R267")
      (value "2K")
      (footprint "R0402")
      (description "RES SMD 2K OHM 1% 1/16W 0402")
      (fields (field (name "MANUFACTURER") "Yageo") (field (name "PART") "2k 1% 0402"))
      (libsource (lib "Resistors") (part "2K 1% 0402"))
    )
    (comp (ref "R268")
      (value "4.3K")
      (footprint "R0402")
      (description "RES SMD 4.3K OHM 1% 1/16W 0402")
      (fields (field (name "MANUFACTURER") "Yageo") (field (name "PART") "4.3K 1% 0402"))
      (libsource (lib "Resistors") (part "4.3K 1% 0402"))
    )
    (comp (ref "R269")
      (value "4.3K")
      (footprint "R0402")
      (description "RES SMD 4.3K OHM 1% 1/16W 0402")
      (fields (field (name "MANUFACTURER") "Yageo") (field (name "PART") "4.3K 1% 0402"))
      (libsource (lib "Resistors") (part "4.3K 1% 0402"))
    )
    (comp (ref "R270")
      (value "4.3K")
      (footprint "R0402")
      (description "RES SMD 4.3K OHM 1% 1/16W 0402")
      (fields (field (name "MANUFACTURER") "Yageo") (field (name "PART") "4.3K 1% 0402"))
      (libsource (lib "Resistors") (part "4.3K 1% 0402"))
    )
    (comp (ref "R271")
      (value "4.3K")
      (footprint "R0402")
      (description "RES SMD 4.3K OHM 1% 1/16W 0402")
      (fields (field (name "MANUFACTURER") "Yageo") (field (name "PART") "4.3K 1% 0402"))
      (libsource (lib "Resistors") (part "4.3K 1% 0402"))
    )
    (comp (ref "R272")
      (value "2K")
      (footprint "R0402")
      (description "RES SMD 2K OHM 1% 1/16W 0402")
      (fields (field (name "MANUFACTURER") "Yageo") (field (name "PART") "2k 1% 0402"))
      (libsource (lib "Resistors") (part "2K 1% 0402"))
    )
    (comp (ref "R273")
      (value "2K")
      (footprint "R0402")
      (description "RES SMD 2K OHM 1% 1/16W 0402")
      (fields (field (name "MANUFACTURER") "Yageo") (field (name "PART") "2k 1% 0402"))
      (libsource (lib "Resistors") (part "2K 1% 0402"))
    )
    (comp (ref "R274")
      (value "2K")
      (footprint "R0402")
      (description "RES SMD 2K OHM 1% 1/16W 0402")
      (fields (field (name "MANUFACTURER") "Yageo") (field (name "PART") "2k 1% 0402"))
      (libsource (lib "Resistors") (part "2K 1% 0402"))
    )
    (comp (ref "R275")
      (value "2K")
      (footprint "R0402")
      (description "RES SMD 2K OHM 1% 1/16W 0402")
      (fields (field (name "MANUFACTURER") "Yageo") (field (name "PART") "2k 1% 0402"))
      (libsource (lib "Resistors") (part "2K 1% 0402"))
    )
    (comp (ref "R276")
      (value "4.3K")
      (footprint "R0402")
      (description "RES SMD 4.3K OHM 1% 1/16W 0402")
      (fields (field (name "MANUFACTURER") "Yageo") (field (name "PART") "4.3K 1% 0402"))
      (libsource (lib "Resistors") (part "4.3K 1% 0402"))
    )
    (comp (ref "R277")
      (value "4.3K")
      (footprint "R0402")
      (description "RES SMD 4.3K OHM 1% 1/16W 0402")
      (fields (field (name "MANUFACTURER") "Yageo") (field (name "PART") "4.3K 1% 0402"))
      (libsource (lib "Resistors") (part "4.3K 1% 0402"))
    )
    (comp (ref "R278")
      (value "4.3K")
      (footprint "R0402")
      (description "RES SMD 4.3K OHM 1% 1/16W 0402")
      (fields (field (name "MANUFACTURER") "Yageo") (field (name "PART") "4.3K 1% 0402"))
      (libsource (lib "Resistors") (part "4.3K 1% 0402"))
    )
    (comp (ref "R279")
      (value "4.3K")
      (footprint "R0402")
      (description "RES SMD 4.3K OHM 1% 1/16W 0402")
      (fields (field (name "MANUFACTURER") "Yageo") (field (name "PART") "4.3K 1% 0402"))
      (libsource (lib "Resistors") (part "4.3K 1% 0402"))
    )
    (comp (ref "R280")
      (value "4.3K")
      (footprint "R0402")
      (description "RES SMD 4.3K OHM 1% 1/16W 0402")
      (fields (field (name "MANUFACTURER") "Yageo") (field (name "PART") "4.3K 1% 0402"))
      (libsource (lib "Resistors") (part "4.3K 1% 0402"))
    )
    (comp (ref "R281")
      (value "4.3K")
      (footprint "R0402")
      (description "RES SMD 4.3K OHM 1% 1/16W 0402")
      (fields (field (name "MANUFACTURER") "Yageo") (field (name "PART") "4.3K 1% 0402"))
      (libsource (lib "Resistors") (part "4.3K 1% 0402"))
    )
    (comp (ref "R282")
      (value "4.3K")
      (footprint "R0402")
      (description "RES SMD 4.3K OHM 1% 1/16W 0402")
      (fields (field (name "MANUFACTURER") "Yageo") (field (name "PART") "4.3K 1% 0402"))
      (libsource (lib "Resistors") (part "4.3K 1% 0402"))
    )
    (comp (ref "R283")
      (value "4.3K")
      (footprint "R0402")
      (description "RES SMD 4.3K OHM 1% 1/16W 0402")
      (fields (field (name "MANUFACTURER") "Yageo") (field (name "PART") "4.3K 1% 0402"))
      (libsource (lib "Resistors") (part "4.3K 1% 0402"))
    )
    (comp (ref "R284")
      (value "2K")
      (footprint "R0402")
      (description "RES SMD 2K OHM 1% 1/16W 0402")
      (fields (field (name "MANUFACTURER") "Yageo") (field (name "PART") "2k 1% 0402"))
      (libsource (lib "Resistors") (part "2K 1% 0402"))
    )
    (comp (ref "R285")
      (value "2K")
      (footprint "R0402")
      (description "RES SMD 2K OHM 1% 1/16W 0402")
      (fields (field (name "MANUFACTURER") "Yageo") (field (name "PART") "2k 1% 0402"))
      (libsource (lib "Resistors") (part "2K 1% 0402"))
    )
    (comp (ref "R286")
      (value "2K")
      (footprint "R0402")
      (description "RES SMD 2K OHM 1% 1/16W 0402")
      (fields (field (name "MANUFACTURER") "Yageo") (field (name "PART") "2k 1% 0402"))
      (libsource (lib "Resistors") (part "2K 1% 0402"))
    )
    (comp (ref "R287")
      (value "2K")
      (footprint "R0402")
      (description "RES SMD 2K OHM 1% 1/16W 0402")
      (fields (field (name "MANUFACTURER") "Yageo") (field (name "PART") "2k 1% 0402"))
      (libsource (lib "Resistors") (part "2K 1% 0402"))
    )
    (comp (ref "R288")
      (value "2K")
      (footprint "R0402")
      (description "RES SMD 2K OHM 1% 1/16W 0402")
      (fields (field (name "MANUFACTURER") "Yageo") (field (name "PART") "2k 1% 0402"))
      (libsource (lib "Resistors") (part "2K 1% 0402"))
    )
    (comp (ref "R289")
      (value "2K")
      (footprint "R0402")
      (description "RES SMD 2K OHM 1% 1/16W 0402")
      (fields (field (name "MANUFACTURER") "Yageo") (field (name "PART") "2k 1% 0402"))
      (libsource (lib "Resistors") (part "2K 1% 0402"))
    )
    (comp (ref "R290")
      (value "2K")
      (footprint "R0402")
      (description "RES SMD 2K OHM 1% 1/16W 0402")
      (fields (field (name "MANUFACTURER") "Yageo") (field (name "PART") "2k 1% 0402"))
      (libsource (lib "Resistors") (part "2K 1% 0402"))
    )
    (comp (ref "R291")
      (value "2K")
      (footprint "R0402")
      (description "RES SMD 2K OHM 1% 1/16W 0402")
      (fields (field (name "MANUFACTURER") "Yageo") (field (name "PART") "2k 1% 0402"))
      (libsource (lib "Resistors") (part "2K 1% 0402"))
    )
    (comp (ref "R292")
      (value "4.3K")
      (footprint "R0402")
      (description "RES SMD 4.3K OHM 1% 1/16W 0402")
      (fields (field (name "MANUFACTURER") "Yageo") (field (name "PART") "4.3K 1% 0402"))
      (libsource (lib "Resistors") (part "4.3K 1% 0402"))
    )
    (comp (ref "R293")
      (value "4.3K")
      (footprint "R0402")
      (description "RES SMD 4.3K OHM 1% 1/16W 0402")
      (fields (field (name "MANUFACTURER") "Yageo") (field (name "PART") "4.3K 1% 0402"))
      (libsource (lib "Resistors") (part "4.3K 1% 0402"))
    )
    (comp (ref "R294")
      (value "4.3K")
      (footprint "R0402")
      (description "RES SMD 4.3K OHM 1% 1/16W 0402")
      (fields (field (name "MANUFACTURER") "Yageo") (field (name "PART") "4.3K 1% 0402"))
      (libsource (lib "Resistors") (part "4.3K 1% 0402"))
    )
    (comp (ref "R295")
      (value "4.3K")
      (footprint "R0402")
      (description "RES SMD 4.3K OHM 1% 1/16W 0402")
      (fields (field (name "MANUFACTURER") "Yageo") (field (name "PART") "4.3K 1% 0402"))
      (libsource (lib "Resistors") (part "4.3K 1% 0402"))
    )
    (comp (ref "U22")
      (value "ST26C32ABTR")
      (footprint "TSSOP16-65P640X120-16N")
      (description "IC RECEIVER 0/4 16TSSOP")
      (fields (field (name "MANUFACTURER") "STM"))
      (libsource (lib "ICs-Interface") (part "ST26C32ABTR"))
    )
    (comp (ref "U23")
      (value "ST26C32ABTR")
      (footprint "TSSOP16-65P640X120-16N")
      (description "IC RECEIVER 0/4 16TSSOP")
      (fields (field (name "MANUFACTURER") "STM"))
      (libsource (lib "ICs-Interface") (part "ST26C32ABTR"))
    )
    (comp (ref "U24")
      (value "ST26C32ABTR")
      (footprint "TSSOP16-65P640X120-16N")
      (description "IC RECEIVER 0/4 16TSSOP")
      (fields (field (name "MANUFACTURER") "STM"))
      (libsource (lib "ICs-Interface") (part "ST26C32ABTR"))
    )
    (comp (ref "U25")
      (value "ST26C32ABTR")
      (footprint "TSSOP16-65P640X120-16N")
      (description "IC RECEIVER 0/4 16TSSOP")
      (fields (field (name "MANUFACTURER") "STM"))
      (libsource (lib "ICs-Interface") (part "ST26C32ABTR"))
    )
  )
  (nets
    (net (code "1") (name "+5VCC") (class "Default")
      (node (ref "C112") (pin "2") (pinfunction "2_2") (pintype "passive"))
      (node (ref "C113") (pin "2") (pinfunction "2_2") (pintype "passive"))
      (node (ref "C114") (pin "2") (pinfunction "2_2") (pintype "passive"))
      (node (ref "C115") (pin "2") (pinfunction "2_2") (pintype "passive"))
      (node (ref "FB1") (pin "1") (pinfunction "1_1") (pintype "passive"))
      (node (ref "U22") (pin "16") (pinfunction "VCC_16") (pintype "power_in"))
      (node (ref "U22") (pin "4") (pinfunction "EN_4") (pintype "input"))
      (node (ref "U23") (pin "16") (pinfunction "VCC_16") (pintype "power_in"))
      (node (ref "U23") (pin "4") (pinfunction "EN_4") (pintype "input"))
      (node (ref "U24") (pin "16") (pinfunction "VCC_16") (pintype "power_in"))
      (node (ref "U24") (pin "4") (pinfunction "EN_4") (pintype "input"))
      (node (ref "U25") (pin "16") (pinfunction "VCC_16") (pintype "power_in"))
      (node (ref "U25") (pin "4") (pinfunction "EN_4") (pintype "input"))
    )
    (net (code "2") (name "/ENC1A_N") (class "Default")
      (node (ref "D19") (pin "A") (pinfunction "A_A") (pintype "passive"))
      (node (ref "J25") (pin "3") (pinfunction "3_3") (pintype "passive"))
      (node (ref "R117") (pin "2") (pinfunction "2_2") (pintype "passive"))
      (node (ref "R118") (pin "2") (pinfunction "2_2") (pintype "passive"))
    )
    (net (code "3") (name "/ENC1A_P") (class "Default")
      (node (ref "D12") (pin "A") (pinfunction "A_A") (pintype "passive"))
      (node (ref "J25") (pin "4") (pinfunction "4_4") (pintype "passive"))
      (node (ref "R17") (pin "1") (pinfunction "1_1") (pintype "passive"))
      (node (ref "R18") (pin "2") (pinfunction "2_2") (pintype "passive"))
    )
    (net (code "4") (name "/ENC1B_N") (class "Default")
      (node (ref "D81") (pin "A") (pinfunction "A_A") (pintype "passive"))
      (node (ref "J25") (pin "1") (pinfunction "1_1") (pintype "passive"))
      (node (ref "R178") (pin "2") (pinfunction "2_2") (pintype "passive"))
      (node (ref "R195") (pin "2") (pinfunction "2_2") (pintype "passive"))
    )
    (net (code "5") (name "/ENC1B_P") (class "Default")
      (node (ref "D20") (pin "A") (pinfunction "A_A") (pintype "passive"))
      (node (ref "J25") (pin "2") (pinfunction "2_2") (pintype "passive"))
      (node (ref "R121") (pin "1") (pinfunction "1_1") (pintype "passive"))
      (node (ref "R127") (pin "2") (pinfunction "2_2") (pintype "passive"))
    )
    (net (code "6") (name "/ENC2A_N") (class "Default")
      (node (ref "D82") (pin "A") (pinfunction "A_A") (pintype "passive"))
      (node (ref "J26") (pin "3") (pinfunction "3_3") (pintype "passive"))
      (node (ref "R179") (pin "2") (pinfunction "2_2") (pintype "passive"))
      (node (ref "R196") (pin "2") (pinfunction "2_2") (pintype "passive"))
    )
    (net (code "7") (name "/ENC2A_P") (class "Default")
      (node (ref "D79") (pin "A") (pinfunction "A_A") (pintype "passive"))
      (node (ref "J26") (pin "4") (pinfunction "4_4") (pintype "passive"))
      (node (ref "R122") (pin "1") (pinfunction "1_1") (pintype "passive"))
      (node (ref "R128") (pin "2") (pinfunction "2_2") (pintype "passive"))
    )
    (net (code "8") (name "/ENC2B_N") (class "Default")
      (node (ref "D83") (pin "A") (pinfunction "A_A") (pintype "passive"))
      (node (ref "J26") (pin "1") (pinfunction "1_1") (pintype "passive"))
      (node (ref "R194") (pin "2") (pinfunction "2_2") (pintype "passive"))
      (node (ref "R199") (pin "2") (pinfunction "2_2") (pintype "passive"))
    )
    (net (code "9") (name "/ENC2B_P") (class "Default")
      (node (ref "D80") (pin "A") (pinfunction "A_A") (pintype "passive"))
      (node (ref "J26") (pin "2") (pinfunction "2_2") (pintype "passive"))
      (node (ref "R123") (pin "1") (pinfunction "1_1") (pintype "passive"))
      (node (ref "R129") (pin "2") (pinfunction "2_2") (pintype "passive"))
    )
    (net (code "10") (name "/ENC3A_N") (class "Default")
      (node (ref "D88") (pin "A") (pinfunction "A_A") (pintype "passive"))
      (node (ref "J27") (pin "3") (pinfunction "3_3") (pintype "passive"))
      (node (ref "R224") (pin "2") (pinfunction "2_2") (pintype "passive"))
      (node (ref "R228") (pin "2") (pinfunction "2_2") (pintype "passive"))
    )
    (net (code "11") (name "/ENC3A_P") (class "Default")
      (node (ref "D84") (pin "A") (pinfunction "A_A") (pintype "passive"))
      (node (ref "J27") (pin "4") (pinfunction "4_4") (pintype "passive"))
      (node (ref "R200") (pin "1") (pinfunction "1_1") (pintype "passive"))
      (node (ref "R208") (pin "2") (pinfunction "2_2") (pintype "passive"))
    )
    (net (code "12") (name "/ENC3B_N") (class "Default")
      (node (ref "D89") (pin "A") (pinfunction "A_A") (pintype "passive"))
      (node (ref "J27") (pin "1") (pinfunction "1_1") (pintype "passive"))
      (node (ref "R225") (pin "2") (pinfunction "2_2") (pintype "passive"))
      (node (ref "R229") (pin "2") (pinfunction "2_2") (pintype "passive"))
    )
    (net (code "13") (name "/ENC3B_P") (class "Default")
      (node (ref "D85") (pin "A") (pinfunction "A_A") (pintype "passive"))
      (node (ref "J27") (pin "2") (pinfunction "2_2") (pintype "passive"))
      (node (ref "R201") (pin "1") (pinfunction "1_1") (pintype "passive"))
      (node (ref "R209") (pin "2") (pinfunction "2_2") (pintype "passive"))
    )
    (net (code "14") (name "/ENC4A_N") (class "Default")
      (node (ref "D90") (pin "A") (pinfunction "A_A") (pintype "passive"))
      (node (ref "J34") (pin "3") (pinfunction "3_3") (pintype "passive"))
      (node (ref "R226") (pin "2") (pinfunction "2_2") (pintype "passive"))
      (node (ref "R230") (pin "2") (pinfunction "2_2") (pintype "passive"))
    )
    (net (code "15") (name "/ENC4A_P") (class "Default")
      (node (ref "D86") (pin "A") (pinfunction "A_A") (pintype "passive"))
      (node (ref "J34") (pin "4") (pinfunction "4_4") (pintype "passive"))
      (node (ref "R202") (pin "1") (pinfunction "1_1") (pintype "passive"))
      (node (ref "R210") (pin "2") (pinfunction "2_2") (pintype "passive"))
    )
    (net (code "16") (name "/ENC4B_N") (class "Default")
      (node (ref "D91") (pin "A") (pinfunction "A_A") (pintype "passive"))
      (node (ref "J34") (pin "1") (pinfunction "1_1") (pintype "passive"))
      (node (ref "R227") (pin "2") (pinfunction "2_2") (pintype "passive"))
      (node (ref "R231") (pin "2") (pinfunction "2_2") (pintype "passive"))
    )
    (net (code "17") (name "/ENC4B_P") (class "Default")
      (node (ref "D87") (pin "A") (pinfunction "A_A") (pintype "passive"))
      (node (ref "J34") (pin "2") (pinfunction "2_2") (pintype "passive"))
      (node (ref "R203") (pin "1") (pinfunction "1_1") (pintype "passive"))
      (node (ref "R211") (pin "2") (pinfunction "2_2") (pintype "passive"))
    )
    (net (code "18") (name "/ENC5A_N") (class "Default")
      (node (ref "D96") (pin "A") (pinfunction "A_A") (pintype "passive"))
      (node (ref "J35") (pin "3") (pinfunction "3_3") (pintype "passive"))
      (node (ref "R256") (pin "2") (pinfunction "2_2") (pintype "passive"))
      (node (ref "R260") (pin "2") (pinfunction "2_2") (pintype "passive"))
    )
    (net (code "19") (name "/ENC5A_P") (class "Default")
      (node (ref "D92") (pin "A") (pinfunction "A_A") (pintype "passive"))
      (node (ref "J35") (pin "4") (pinfunction "4_4") (pintype "passive"))
      (node (ref "R232") (pin "1") (pinfunction "1_1") (pintype "passive"))
      (node (ref "R240") (pin "2") (pinfunction "2_2") (pintype "passive"))
    )
    (net (code "20") (name "/ENC5B_N") (class "Default")
      (node (ref "D97") (pin "A") (pinfunction "A_A") (pintype "passive"))
      (node (ref "J35") (pin "1") (pinfunction "1_1") (pintype "passive"))
      (node (ref "R257") (pin "2") (pinfunction "2_2") (pintype "passive"))
      (node (ref "R261") (pin "2") (pinfunction "2_2") (pintype "passive"))
    )
    (net (code "21") (name "/ENC5B_P") (class "Default")
      (node (ref "D93") (pin "A") (pinfunction "A_A") (pintype "passive"))
      (node (ref "J35") (pin "2") (pinfunction "2_2") (pintype "passive"))
      (node (ref "R233") (pin "1") (pinfunction "1_1") (pintype "passive"))
      (node (ref "R241") (pin "2") (pinfunction "2_2") (pintype "passive"))
    )
    (net (code "22") (name "/ENC6A_N") (class "Default")
      (node (ref "D98") (pin "A") (pinfunction "A_A") (pintype "passive"))
      (node (ref "J36") (pin "3") (pinfunction "3_3") (pintype "passive"))
      (node (ref "R258") (pin "2") (pinfunction "2_2") (pintype "passive"))
      (node (ref "R262") (pin "2") (pinfunction "2_2") (pintype "passive"))
    )
    (net (code "23") (name "/ENC6A_P") (class "Default")
      (node (ref "D94") (pin "A") (pinfunction "A_A") (pintype "passive"))
      (node (ref "J36") (pin "4") (pinfunction "4_4") (pintype "passive"))
      (node (ref "R234") (pin "1") (pinfunction "1_1") (pintype "passive"))
      (node (ref "R242") (pin "2") (pinfunction "2_2") (pintype "passive"))
    )
    (net (code "24") (name "/ENC6B_N") (class "Default")
      (node (ref "D99") (pin "A") (pinfunction "A_A") (pintype "passive"))
      (node (ref "J36") (pin "1") (pinfunction "1_1") (pintype "passive"))
      (node (ref "R259") (pin "2") (pinfunction "2_2") (pintype "passive"))
      (node (ref "R263") (pin "2") (pinfunction "2_2") (pintype "passive"))
    )
    (net (code "25") (name "/ENC6B_P") (class "Default")
      (node (ref "D95") (pin "A") (pinfunction "A_A") (pintype "passive"))
      (node (ref "J36") (pin "2") (pinfunction "2_2") (pintype "passive"))
      (node (ref "R235") (pin "1") (pinfunction "1_1") (pintype "passive"))
      (node (ref "R243") (pin "2") (pinfunction "2_2") (pintype "passive"))
    )
    (net (code "26") (name "/ENC7A_N") (class "Default")
      (node (ref "D104") (pin "A") (pinfunction "A_A") (pintype "passive"))
      (node (ref "J37") (pin "3") (pinfunction "3_3") (pintype "passive"))
      (node (ref "R288") (pin "2") (pinfunction "2_2") (pintype "passive"))
      (node (ref "R292") (pin "2") (pinfunction "2_2") (pintype "passive"))
    )
    (net (code "27") (name "/ENC7A_P") (class "Default")
      (node (ref "D100") (pin "A") (pinfunction "A_A") (pintype "passive"))
      (node (ref "J37") (pin "4") (pinfunction "4_4") (pintype "passive"))
      (node (ref "R264") (pin "1") (pinfunction "1_1") (pintype "passive"))
      (node (ref "R272") (pin "2") (pinfunction "2_2") (pintype "passive"))
    )
    (net (code "28") (name "/ENC7B_N") (class "Default")
      (node (ref "D105") (pin "A") (pinfunction "A_A") (pintype "passive"))
      (node (ref "J37") (pin "1") (pinfunction "1_1") (pintype "passive"))
      (node (ref "R289") (pin "2") (pinfunction "2_2") (pintype "passive"))
      (node (ref "R293") (pin "2") (pinfunction "2_2") (pintype "passive"))
    )
    (net (code "29") (name "/ENC7B_P") (class "Default")
      (node (ref "D101") (pin "A") (pinfunction "A_A") (pintype "passive"))
      (node (ref "J37") (pin "2") (pinfunction "2_2") (pintype "passive"))
      (node (ref "R265") (pin "1") (pinfunction "1_1") (pintype "passive"))
      (node (ref "R273") (pin "2") (pinfunction "2_2") (pintype "passive"))
    )
    (net (code "30") (name "/ENC8A_N") (class "Default")
      (node (ref "D106") (pin "A") (pinfunction "A_A") (pintype "passive"))
      (node (ref "J38") (pin "3") (pinfunction "3_3") (pintype "passive"))
      (node (ref "R290") (pin "2") (pinfunction "2_2") (pintype "passive"))
      (node (ref "R294") (pin "2") (pinfunction "2_2") (pintype "passive"))
    )
    (net (code "31") (name "/ENC8A_P") (class "Default")
      (node (ref "D102") (pin "A") (pinfunction "A_A") (pintype "passive"))
      (node (ref "J38") (pin "4") (pinfunction "4_4") (pintype "passive"))
      (node (ref "R266") (pin "1") (pinfunction "1_1") (pintype "passive"))
      (node (ref "R274") (pin "2") (pinfunction "2_2") (pintype "passive"))
    )
    (net (code "32") (name "/ENC8B_N") (class "Default")
      (node (ref "D107") (pin "A") (pinfunction "A_A") (pintype "passive"))
      (node (ref "J38") (pin "1") (pinfunction "1_1") (pintype "passive"))
      (node (ref "R291") (pin "2") (pinfunction "2_2") (pintype "passive"))
      (node (ref "R295") (pin "2") (pinfunction "2_2") (pintype "passive"))
    )
    (net (code "33") (name "/ENC8B_P") (class "Default")
      (node (ref "D103") (pin "A") (pinfunction "A_A") (pintype "passive"))
      (node (ref "J38") (pin "2") (pinfunction "2_2") (pintype "passive"))
      (node (ref "R267") (pin "1") (pinfunction "1_1") (pintype "passive"))
      (node (ref "R275") (pin "2") (pinfunction "2_2") (pintype "passive"))
    )
    (net (code "34") (name "/ENCA1") (class "Default")
      (node (ref "U23") (pin "3") (pinfunction "OUT_3") (pintype "output"))
    )
    (net (code "35") (name "/ENCA2") (class "Default")
      (node (ref "U23") (pin "11") (pinfunction "OUT_11") (pintype "output"))
    )
    (net (code "36") (name "/ENCA3") (class "Default")
      (node (ref "U22") (pin "3") (pinfunction "OUT_3") (pintype "output"))
    )
    (net (code "37") (name "/ENCA4") (class "Default")
      (node (ref "U22") (pin "13") (pinfunction "OUT_13") (pintype "output"))
    )
    (net (code "38") (name "/ENCA5") (class "Default")
      (node (ref "U24") (pin "3") (pinfunction "OUT_3") (pintype "output"))
    )
    (net (code "39") (name "/ENCA6") (class "Default")
      (node (ref "U24") (pin "11") (pinfunction "OUT_11") (pintype "output"))
    )
    (net (code "40") (name "/ENCA7") (class "Default")
      (node (ref "U25") (pin "3") (pinfunction "OUT_3") (pintype "output"))
    )
    (net (code "41") (name "/ENCA8") (class "Default")
      (node (ref "U25") (pin "11") (pinfunction "OUT_11") (pintype "output"))
    )
    (net (code "43") (name "/ENCB1") (class "Default")
      (node (ref "U23") (pin "5") (pinfunction "OUT_5") (pintype "output"))
    )
    (net (code "44") (name "/ENCB2") (class "Default")
      (node (ref "U23") (pin "13") (pinfunction "OUT_13") (pintype "output"))
    )
    (net (code "45") (name "/ENCB3") (class "Default")
      (node (ref "U22") (pin "5") (pinfunction "OUT_5") (pintype "output"))
    )
    (net (code "46") (name "/ENCB4") (class "Default")
      (node (ref "U22") (pin "11") (pinfunction "OUT_11") (pintype "output"))
    )
    (net (code "47") (name "/ENCB5") (class "Default")
      (node (ref "U24") (pin "5") (pinfunction "OUT_5") (pintype "output"))
    )
    (net (code "48") (name "/ENCB6") (class "Default")
      (node (ref "U24") (pin "13") (pinfunction "OUT_13") (pintype "output"))
    )
    (net (code "49") (name "/ENCB7") (class "Default")
      (node (ref "U25") (pin "5") (pinfunction "OUT_5") (pintype "output"))
    )
    (net (code "50") (name "/ENCB8") (class "Default")
      (node (ref "U25") (pin "13") (pinfunction "OUT_13") (pintype "output"))
    )
    (net (code "52") (name "5Venc") (class "Default")
      (node (ref "C108") (pin "2") (pinfunction "2_2") (pintype "passive"))
      (node (ref "C116") (pin "2") (pinfunction "2_2") (pintype "passive"))
      (node (ref "C117") (pin "2") (pinfunction "2_2") (pintype "passive"))
      (node (ref "C118") (pin "2") (pinfunction "2_2") (pintype "passive"))
      (node (ref "C119") (pin "2") (pinfunction "2_2") (pintype "passive"))
      (node (ref "C120") (pin "2") (pinfunction "2_2") (pintype "passive"))
      (node (ref "C126") (pin "2") (pinfunction "2_2") (pintype "passive"))
      (node (ref "C127") (pin "2") (pinfunction "2_2") (pintype "passive"))
      (node (ref "C128") (pin "2") (pinfunction "2_2") (pintype "passive"))
      (node (ref "FB1") (pin "2") (pinfunction "2_2") (pintype "passive"))
      (node (ref "J25") (pin "6") (pinfunction "6_6") (pintype "passive"))
      (node (ref "J26") (pin "6") (pinfunction "6_6") (pintype "passive"))
      (node (ref "J27") (pin "6") (pinfunction "6_6") (pintype "passive"))
      (node (ref "J34") (pin "6") (pinfunction "6_6") (pintype "passive"))
      (node (ref "J35") (pin "6") (pinfunction "6_6") (pintype "passive"))
      (node (ref "J36") (pin "6") (pinfunction "6_6") (pintype "passive"))
      (node (ref "J37") (pin "6") (pinfunction "6_6") (pintype "passive"))
      (node (ref "J38") (pin "6") (pinfunction "6_6") (pintype "passive"))
      (node (ref "R105") (pin "2") (pinfunction "2_2") (pintype "passive"))
      (node (ref "R124") (pin "2") (pinfunction "2_2") (pintype "passive"))
      (node (ref "R125") (pin "2") (pinfunction "2_2") (pintype "passive"))
      (node (ref "R126") (pin "2") (pinfunction "2_2") (pintype "passive"))
      (node (ref "R130") (pin "2") (pinfunction "2_2") (pintype "passive"))
      (node (ref "R131") (pin "2") (pinfunction "2_2") (pintype "passive"))
      (node (ref "R132") (pin "2") (pinfunction "2_2") (pintype "passive"))
      (node (ref "R16") (pin "2") (pinfunction "2_2") (pintype "passive"))
      (node (ref "R204") (pin "2") (pinfunction "2_2") (pintype "passive"))
      (node (ref "R205") (pin "2") (pinfunction "2_2") (pintype "passive"))
      (node (ref "R206") (pin "2") (pinfunction "2_2") (pintype "passive"))
      (node (ref "R207") (pin "2") (pinfunction "2_2") (pintype "passive"))
      (node (ref "R212") (pin "2") (pinfunction "2_2") (pintype "passive"))
      (node (ref "R213") (pin "2") (pinfunction "2_2") (pintype "passive"))
      (node (ref "R214") (pin "2") (pinfunction "2_2") (pintype "passive"))
      (node (ref "R215") (pin "2") (pinfunction "2_2") (pintype "passive"))
      (node (ref "R236") (pin "2") (pinfunction "2_2") (pintype "passive"))
      (node (ref "R237") (pin "2") (pinfunction "2_2") (pintype "passive"))
      (node (ref "R238") (pin "2") (pinfunction "2_2") (pintype "passive"))
      (node (ref "R239") (pin "2") (pinfunction "2_2") (pintype "passive"))
      (node (ref "R244") (pin "2") (pinfunction "2_2") (pintype "passive"))
      (node (ref "R245") (pin "2") (pinfunction "2_2") (pintype "passive"))
      (node (ref "R246") (pin "2") (pinfunction "2_2") (pintype "passive"))
      (node (ref "R247") (pin "2") (pinfunction "2_2") (pintype "passive"))
      (node (ref "R268") (pin "2") (pinfunction "2_2") (pintype "passive"))
      (node (ref "R269") (pin "2") (pinfunction "2_2") (pintype "passive"))
      (node (ref "R270") (pin "2") (pinfunction "2_2") (pintype "passive"))
      (node (ref "R271") (pin "2") (pinfunction "2_2") (pintype "passive"))
      (node (ref "R276") (pin "2") (pinfunction "2_2") (pintype "passive"))
      (node (ref "R277") (pin "2") (pinfunction "2_2") (pintype "passive"))
      (node (ref "R278") (pin "2") (pinfunction "2_2") (pintype "passive"))
      (node (ref "R279") (pin "2") (pinfunction "2_2") (pintype "passive"))
    )
    (net (code "53") (name "GND") (class "Default")
      (node (ref "C108") (pin "1") (pinfunction "1_1") (pintype "passive"))
      (node (ref "C112") (pin "1") (pinfunction "1_1") (pintype "passive"))
      (node (ref "C113") (pin "1") (pinfunction "1_1") (pintype "passive"))
      (node (ref "C114") (pin "1") (pinfunction "1_1") (pintype "passive"))
      (node (ref "C115") (pin "1") (pinfunction "1_1") (pintype "passive"))
      (node (ref "C116") (pin "1") (pinfunction "1_1") (pintype "passive"))
      (node (ref "C117") (pin "1") (pinfunction "1_1") (pintype "passive"))
      (node (ref "C118") (pin "1") (pinfunction "1_1") (pintype "passive"))
      (node (ref "C119") (pin "1") (pinfunction "1_1") (pintype "passive"))
      (node (ref "C120") (pin "1") (pinfunction "1_1") (pintype "passive"))
      (node (ref "C126") (pin "1") (pinfunction "1_1") (pintype "passive"))
      (node (ref "C127") (pin "1") (pinfunction "1_1") (pintype "passive"))
      (node (ref "C128") (pin "1") (pinfunction "1_1") (pintype "passive"))
      (node (ref "D100") (pin "K") (pinfunction "K_K") (pintype "passive"))
      (node (ref "D101") (pin "K") (pinfunction "K_K") (pintype "passive"))
      (node (ref "D102") (pin "K") (pinfunction "K_K") (pintype "passive"))
      (node (ref "D103") (pin "K") (pinfunction "K_K") (pintype "passive"))
      (node (ref "D104") (pin "K") (pinfunction "K_K") (pintype "passive"))
      (node (ref "D105") (pin "K") (pinfunction "K_K") (pintype "passive"))
      (node (ref "D106") (pin "K") (pinfunction "K_K") (pintype "passive"))
      (node (ref "D107") (pin "K") (pinfunction "K_K") (pintype "passive"))
      (node (ref "D12") (pin "K") (pinfunction "K_K") (pintype "passive"))
      (node (ref "D19") (pin "K") (pinfunction "K_K") (pintype "passive"))
      (node (ref "D20") (pin "K") (pinfunction "K_K") (pintype "passive"))
      (node (ref "D79") (pin "K") (pinfunction "K_K") (pintype "passive"))
      (node (ref "D80") (pin "K") (pinfunction "K_K") (pintype "passive"))
      (node (ref "D81") (pin "K") (pinfunction "K_K") (pintype "passive"))
      (node (ref "D82") (pin "K") (pinfunction "K_K") (pintype "passive"))
      (node (ref "D83") (pin "K") (pinfunction "K_K") (pintype "passive"))
      (node (ref "D84") (pin "K") (pinfunction "K_K") (pintype "passive"))
      (node (ref "D85") (pin "K") (pinfunction "K_K") (pintype "passive"))
      (node (ref "D86") (pin "K") (pinfunction "K_K") (pintype "passive"))
      (node (ref "D87") (pin "K") (pinfunction "K_K") (pintype "passive"))
      (node (ref "D88") (pin "K") (pinfunction "K_K") (pintype "passive"))
      (node (ref "D89") (pin "K") (pinfunction "K_K") (pintype "passive"))
      (node (ref "D90") (pin "K") (pinfunction "K_K") (pintype "passive"))
      (node (ref "D91") (pin "K") (pinfunction "K_K") (pintype "passive"))
      (node (ref "D92") (pin "K") (pinfunction "K_K") (pintype "passive"))
      (node (ref "D93") (pin "K") (pinfunction "K_K") (pintype "passive"))
      (node (ref "D94") (pin "K") (pinfunction "K_K") (pintype "passive"))
      (node (ref "D95") (pin "K") (pinfunction "K_K") (pintype "passive"))
      (node (ref "D96") (pin "K") (pinfunction "K_K") (pintype "passive"))
      (node (ref "D97") (pin "K") (pinfunction "K_K") (pintype "passive"))
      (node (ref "D98") (pin "K") (pinfunction "K_K") (pintype "passive"))
      (node (ref "D99") (pin "K") (pinfunction "K_K") (pintype "passive"))
      (node (ref "J25") (pin "5") (pinfunction "5_5") (pintype "passive"))
      (node (ref "J26") (pin "5") (pinfunction "5_5") (pintype "passive"))
      (node (ref "J27") (pin "5") (pinfunction "5_5") (pintype "passive"))
      (node (ref "J34") (pin "5") (pinfunction "5_5") (pintype "passive"))
      (node (ref "J35") (pin "5") (pinfunction "5_5") (pintype "passive"))
      (node (ref "J36") (pin "5") (pinfunction "5_5") (pintype "passive"))
      (node (ref "J37") (pin "5") (pinfunction "5_5") (pintype "passive"))
      (node (ref "J38") (pin "5") (pinfunction "5_5") (pintype "passive"))
      (node (ref "R118") (pin "1") (pinfunction "1_1") (pintype "passive"))
      (node (ref "R146") (pin "1") (pinfunction "1_1") (pintype "passive"))
      (node (ref "R147") (pin "1") (pinfunction "1_1") (pintype "passive"))
      (node (ref "R153") (pin "1") (pinfunction "1_1") (pintype "passive"))
      (node (ref "R195") (pin "1") (pinfunction "1_1") (pintype "passive"))
      (node (ref "R196") (pin "1") (pinfunction "1_1") (pintype "passive"))
      (node (ref "R199") (pin "1") (pinfunction "1_1") (pintype "passive"))
      (node (ref "R216") (pin "1") (pinfunction "1_1") (pintype "passive"))
      (node (ref "R217") (pin "1") (pinfunction "1_1") (pintype "passive"))
      (node (ref "R218") (pin "1") (pinfunction "1_1") (pintype "passive"))
      (node (ref "R219") (pin "1") (pinfunction "1_1") (pintype "passive"))
      (node (ref "R228") (pin "1") (pinfunction "1_1") (pintype "passive"))
      (node (ref "R229") (pin "1") (pinfunction "1_1") (pintype "passive"))
      (node (ref "R230") (pin "1") (pinfunction "1_1") (pintype "passive"))
      (node (ref "R231") (pin "1") (pinfunction "1_1") (pintype "passive"))
      (node (ref "R248") (pin "1") (pinfunction "1_1") (pintype "passive"))
      (node (ref "R249") (pin "1") (pinfunction "1_1") (pintype "passive"))
      (node (ref "R250") (pin "1") (pinfunction "1_1") (pintype "passive"))
      (node (ref "R251") (pin "1") (pinfunction "1_1") (pintype "passive"))
      (node (ref "R260") (pin "1") (pinfunction "1_1") (pintype "passive"))
      (node (ref "R261") (pin "1") (pinfunction "1_1") (pintype "passive"))
      (node (ref "R262") (pin "1") (pinfunction "1_1") (pintype "passive"))
      (node (ref "R263") (pin "1") (pinfunction "1_1") (pintype "passive"))
      (node (ref "R280") (pin "1") (pinfunction "1_1") (pintype "passive"))
      (node (ref "R281") (pin "1") (pinfunction "1_1") (pintype "passive"))
      (node (ref "R282") (pin "1") (pinfunction "1_1") (pintype "passive"))
      (node (ref "R283") (pin "1") (pinfunction "1_1") (pintype "passive"))
      (node (ref "R292") (pin "1") (pinfunction "1_1") (pintype "passive"))
      (node (ref "R293") (pin "1") (pinfunction "1_1") (pintype "passive"))
      (node (ref "R294") (pin "1") (pinfunction "1_1") (pintype "passive"))
      (node (ref "R295") (pin "1") (pinfunction "1_1") (pintype "passive"))
      (node (ref "R83") (pin "1") (pinfunction "1_1") (pintype "passive"))
      (node (ref "U22") (pin "12") (pinfunction "nEN_12") (pintype "input"))
      (node (ref "U22") (pin "8") (pinfunction "GND_8") (pintype "power_in"))
      (node (ref "U23") (pin "12") (pinfunction "nEN_12") (pintype "input"))
      (node (ref "U23") (pin "8") (pinfunction "GND_8") (pintype "power_in"))
      (node (ref "U24") (pin "12") (pinfunction "nEN_12") (pintype "input"))
      (node (ref "U24") (pin "8") (pinfunction "GND_8") (pintype "power_in"))
      (node (ref "U25") (pin "12") (pinfunction "nEN_12") (pintype "input"))
      (node (ref "U25") (pin "8") (pinfunction "GND_8") (pintype "power_in"))
    )
    (net (code "54") (name "Net-(R18-Pad1)") (class "Default")
      (node (ref "R18") (pin "1") (pinfunction "1_1") (pintype "passive"))
      (node (ref "R83") (pin "2") (pinfunction "2_2") (pintype "passive"))
    )
    (net (code "55") (name "Net-(R105-Pad1)") (class "Default")
      (node (ref "R105") (pin "1") (pinfunction "1_1") (pintype "passive"))
      (node (ref "R106") (pin "2") (pinfunction "2_2") (pintype "passive"))
    )
    (net (code "56") (name "Net-(R127-Pad1)") (class "Default")
      (node (ref "R127") (pin "1") (pinfunction "1_1") (pintype "passive"))
      (node (ref "R146") (pin "2") (pinfunction "2_2") (pintype "passive"))
    )
    (net (code "57") (name "Net-(R128-Pad1)") (class "Default")
      (node (ref "R128") (pin "1") (pinfunction "1_1") (pintype "passive"))
      (node (ref "R147") (pin "2") (pinfunction "2_2") (pintype "passive"))
    )
    (net (code "58") (name "Net-(R129-Pad1)") (class "Default")
      (node (ref "R129") (pin "1") (pinfunction "1_1") (pintype "passive"))
      (node (ref "R153") (pin "2") (pinfunction "2_2") (pintype "passive"))
    )
    (net (code "59") (name "Net-(R130-Pad1)") (class "Default")
      (node (ref "R130") (pin "1") (pinfunction "1_1") (pintype "passive"))
      (node (ref "R159") (pin "2") (pinfunction "2_2") (pintype "passive"))
    )
    (net (code "60") (name "Net-(R131-Pad1)") (class "Default")
      (node (ref "R131") (pin "1") (pinfunction "1_1") (pintype "passive"))
      (node (ref "R160") (pin "2") (pinfunction "2_2") (pintype "passive"))
    )
    (net (code "61") (name "Net-(R132-Pad1)") (class "Default")
      (node (ref "R132") (pin "1") (pinfunction "1_1") (pintype "passive"))
      (node (ref "R161") (pin "2") (pinfunction "2_2") (pintype "passive"))
    )
    (net (code "62") (name "Net-(R208-Pad1)") (class "Default")
      (node (ref "R208") (pin "1") (pinfunction "1_1") (pintype "passive"))
      (node (ref "R216") (pin "2") (pinfunction "2_2") (pintype "passive"))
    )
    (net (code "63") (name "Net-(R209-Pad1)") (class "Default")
      (node (ref "R209") (pin "1") (pinfunction "1_1") (pintype "passive"))
      (node (ref "R217") (pin "2") (pinfunction "2_2") (pintype "passive"))
    )
    (net (code "64") (name "Net-(R210-Pad1)") (class "Default")
      (node (ref "R210") (pin "1") (pinfunction "1_1") (pintype "passive"))
      (node (ref "R218") (pin "2") (pinfunction "2_2") (pintype "passive"))
    )
    (net (code "65") (name "Net-(R211-Pad1)") (class "Default")
      (node (ref "R211") (pin "1") (pinfunction "1_1") (pintype "passive"))
      (node (ref "R219") (pin "2") (pinfunction "2_2") (pintype "passive"))
    )
    (net (code "66") (name "Net-(R212-Pad1)") (class "Default")
      (node (ref "R212") (pin "1") (pinfunction "1_1") (pintype "passive"))
      (node (ref "R220") (pin "2") (pinfunction "2_2") (pintype "passive"))
    )
    (net (code "67") (name "Net-(R213-Pad1)") (class "Default")
      (node (ref "R213") (pin "1") (pinfunction "1_1") (pintype "passive"))
      (node (ref "R221") (pin "2") (pinfunction "2_2") (pintype "passive"))
    )
    (net (code "68") (name "Net-(R214-Pad1)") (class "Default")
      (node (ref "R214") (pin "1") (pinfunction "1_1") (pintype "passive"))
      (node (ref "R222") (pin "2") (pinfunction "2_2") (pintype "passive"))
    )
    (net (code "69") (name "Net-(R215-Pad1)") (class "Default")
      (node (ref "R215") (pin "1") (pinfunction "1_1") (pintype "passive"))
      (node (ref "R223") (pin "2") (pinfunction "2_2") (pintype "passive"))
    )
    (net (code "70") (name "Net-(R240-Pad1)") (class "Default")
      (node (ref "R240") (pin "1") (pinfunction "1_1") (pintype "passive"))
      (node (ref "R248") (pin "2") (pinfunction "2_2") (pintype "passive"))
    )
    (net (code "71") (name "Net-(R241-Pad1)") (class "Default")
      (node (ref "R241") (pin "1") (pinfunction "1_1") (pintype "passive"))
      (node (ref "R249") (pin "2") (pinfunction "2_2") (pintype "passive"))
    )
    (net (code "72") (name "Net-(R242-Pad1)") (class "Default")
      (node (ref "R242") (pin "1") (pinfunction "1_1") (pintype "passive"))
      (node (ref "R250") (pin "2") (pinfunction "2_2") (pintype "passive"))
    )
    (net (code "73") (name "Net-(R243-Pad1)") (class "Default")
      (node (ref "R243") (pin "1") (pinfunction "1_1") (pintype "passive"))
      (node (ref "R251") (pin "2") (pinfunction "2_2") (pintype "passive"))
    )
    (net (code "74") (name "Net-(R244-Pad1)") (class "Default")
      (node (ref "R244") (pin "1") (pinfunction "1_1") (pintype "passive"))
      (node (ref "R252") (pin "2") (pinfunction "2_2") (pintype "passive"))
    )
    (net (code "75") (name "Net-(R245-Pad1)") (class "Default")
      (node (ref "R245") (pin "1") (pinfunction "1_1") (pintype "passive"))
      (node (ref "R253") (pin "2") (pinfunction "2_2") (pintype "passive"))
    )
    (net (code "76") (name "Net-(R246-Pad1)") (class "Default")
      (node (ref "R246") (pin "1") (pinfunction "1_1") (pintype "passive"))
      (node (ref "R254") (pin "2") (pinfunction "2_2") (pintype "passive"))
    )
    (net (code "77") (name "Net-(R247-Pad1)") (class "Default")
      (node (ref "R247") (pin "1") (pinfunction "1_1") (pintype "passive"))
      (node (ref "R255") (pin "2") (pinfunction "2_2") (pintype "passive"))
    )
    (net (code "78") (name "Net-(R272-Pad1)") (class "Default")
      (node (ref "R272") (pin "1") (pinfunction "1_1") (pintype "passive"))
      (node (ref "R280") (pin "2") (pinfunction "2_2") (pintype "passive"))
    )
    (net (code "79") (name "Net-(R273-Pad1)") (class "Default")
      (node (ref "R273") (pin "1") (pinfunction "1_1") (pintype "passive"))
      (node (ref "R281") (pin "2") (pinfunction "2_2") (pintype "passive"))
    )
    (net (code "80") (name "Net-(R274-Pad1)") (class "Default")
      (node (ref "R274") (pin "1") (pinfunction "1_1") (pintype "passive"))
      (node (ref "R282") (pin "2") (pinfunction "2_2") (pintype "passive"))
    )
    (net (code "81") (name "Net-(R275-Pad1)") (class "Default")
      (node (ref "R275") (pin "1") (pinfunction "1_1") (pintype "passive"))
      (node (ref "R283") (pin "2") (pinfunction "2_2") (pintype "passive"))
    )
    (net (code "82") (name "Net-(R276-Pad1)") (class "Default")
      (node (ref "R276") (pin "1") (pinfunction "1_1") (pintype "passive"))
      (node (ref "R284") (pin "2") (pinfunction "2_2") (pintype "passive"))
    )
    (net (code "83") (name "Net-(R277-Pad1)") (class "Default")
      (node (ref "R277") (pin "1") (pinfunction "1_1") (pintype "passive"))
      (node (ref "R285") (pin "2") (pinfunction "2_2") (pintype "passive"))
    )
    (net (code "84") (name "Net-(R278-Pad1)") (class "Default")
      (node (ref "R278") (pin "1") (pinfunction "1_1") (pintype "passive"))
      (node (ref "R286") (pin "2") (pinfunction "2_2") (pintype "passive"))
    )
    (net (code "85") (name "Net-(R279-Pad1)") (class "Default")
      (node (ref "R279") (pin "1") (pinfunction "1_1") (pintype "passive"))
      (node (ref "R287") (pin "2") (pinfunction "2_2") (pintype "passive"))
    )
    (net (code "86") (name "Net-(U22A-IN+)") (class "Default")
      (node (ref "R200") (pin "2") (pinfunction "2_2") (pintype "passive"))
      (node (ref "R204") (pin "1") (pinfunction "1_1") (pintype "passive"))
      (node (ref "U22") (pin "2") (pinfunction "IN+_2") (pintype "input"))
    )
    (net (code "87") (name "Net-(U22A-IN-)") (class "Default")
      (node (ref "R220") (pin "1") (pinfunction "1_1") (pintype "passive"))
      (node (ref "R224") (pin "1") (pinfunction "1_1") (pintype "passive"))
      (node (ref "U22") (pin "1") (pinfunction "IN-_1") (pintype "input"))
    )
    (net (code "88") (name "Net-(U22B-IN+)") (class "Default")
      (node (ref "R201") (pin "2") (pinfunction "2_2") (pintype "passive"))
      (node (ref "R205") (pin "1") (pinfunction "1_1") (pintype "passive"))
      (node (ref "U22") (pin "6") (pinfunction "IN+_6") (pintype "input"))
    )
    (net (code "89") (name "Net-(U22B-IN-)") (class "Default")
      (node (ref "R221") (pin "1") (pinfunction "1_1") (pintype "passive"))
      (node (ref "R225") (pin "1") (pinfunction "1_1") (pintype "passive"))
      (node (ref "U22") (pin "7") (pinfunction "IN-_7") (pintype "input"))
    )
    (net (code "90") (name "Net-(U22C-IN+)") (class "Default")
      (node (ref "R203") (pin "2") (pinfunction "2_2") (pintype "passive"))
      (node (ref "R207") (pin "1") (pinfunction "1_1") (pintype "passive"))
      (node (ref "U22") (pin "10") (pinfunction "IN+_10") (pintype "input"))
    )
    (net (code "91") (name "Net-(U22C-IN-)") (class "Default")
      (node (ref "R223") (pin "1") (pinfunction "1_1") (pintype "passive"))
      (node (ref "R227") (pin "1") (pinfunction "1_1") (pintype "passive"))
      (node (ref "U22") (pin "9") (pinfunction "IN-_9") (pintype "input"))
    )
    (net (code "92") (name "Net-(U22D-IN+)") (class "Default")
      (node (ref "R202") (pin "2") (pinfunction "2_2") (pintype "passive"))
      (node (ref "R206") (pin "1") (pinfunction "1_1") (pintype "passive"))
      (node (ref "U22") (pin "14") (pinfunction "IN+_14") (pintype "input"))
    )
    (net (code "93") (name "Net-(U22D-IN-)") (class "Default")
      (node (ref "R222") (pin "1") (pinfunction "1_1") (pintype "passive"))
      (node (ref "R226") (pin "1") (pinfunction "1_1") (pintype "passive"))
      (node (ref "U22") (pin "15") (pinfunction "IN-_15") (pintype "input"))
    )
    (net (code "94") (name "Net-(U23A-IN+)") (class "Default")
      (node (ref "R16") (pin "1") (pinfunction "1_1") (pintype "passive"))
      (node (ref "R17") (pin "2") (pinfunction "2_2") (pintype "passive"))
      (node (ref "U23") (pin "2") (pinfunction "IN+_2") (pintype "input"))
    )
    (net (code "95") (name "Net-(U23A-IN-)") (class "Default")
      (node (ref "R106") (pin "1") (pinfunction "1_1") (pintype "passive"))
      (node (ref "R117") (pin "1") (pinfunction "1_1") (pintype "passive"))
      (node (ref "U23") (pin "1") (pinfunction "IN-_1") (pintype "input"))
    )
    (net (code "96") (name "Net-(U23B-IN+)") (class "Default")
      (node (ref "R121") (pin "2") (pinfunction "2_2") (pintype "passive"))
      (node (ref "R124") (pin "1") (pinfunction "1_1") (pintype "passive"))
      (node (ref "U23") (pin "6") (pinfunction "IN+_6") (pintype "input"))
    )
    (net (code "97") (name "Net-(U23B-IN-)") (class "Default")
      (node (ref "R159") (pin "1") (pinfunction "1_1") (pintype "passive"))
      (node (ref "R178") (pin "1") (pinfunction "1_1") (pintype "passive"))
      (node (ref "U23") (pin "7") (pinfunction "IN-_7") (pintype "input"))
    )
    (net (code "98") (name "Net-(U23C-IN+)") (class "Default")
      (node (ref "R122") (pin "2") (pinfunction "2_2") (pintype "passive"))
      (node (ref "R125") (pin "1") (pinfunction "1_1") (pintype "passive"))
      (node (ref "U23") (pin "10") (pinfunction "IN+_10") (pintype "input"))
    )
    (net (code "99") (name "Net-(U23C-IN-)") (class "Default")
      (node (ref "R160") (pin "1") (pinfunction "1_1") (pintype "passive"))
      (node (ref "R179") (pin "1") (pinfunction "1_1") (pintype "passive"))
      (node (ref "U23") (pin "9") (pinfunction "IN-_9") (pintype "input"))
    )
    (net (code "100") (name "Net-(U23D-IN+)") (class "Default")
      (node (ref "R123") (pin "2") (pinfunction "2_2") (pintype "passive"))
      (node (ref "R126") (pin "1") (pinfunction "1_1") (pintype "passive"))
      (node (ref "U23") (pin "14") (pinfunction "IN+_14") (pintype "input"))
    )
    (net (code "101") (name "Net-(U23D-IN-)") (class "Default")
      (node (ref "R161") (pin "1") (pinfunction "1_1") (pintype "passive"))
      (node (ref "R194") (pin "1") (pinfunction "1_1") (pintype "passive"))
      (node (ref "U23") (pin "15") (pinfunction "IN-_15") (pintype "input"))
    )
    (net (code "102") (name "Net-(U24A-IN+)") (class "Default")
      (node (ref "R232") (pin "2") (pinfunction "2_2") (pintype "passive"))
      (node (ref "R236") (pin "1") (pinfunction "1_1") (pintype "passive"))
      (node (ref "U24") (pin "2") (pinfunction "IN+_2") (pintype "input"))
    )
    (net (code "103") (name "Net-(U24A-IN-)") (class "Default")
      (node (ref "R252") (pin "1") (pinfunction "1_1") (pintype "passive"))
      (node (ref "R256") (pin "1") (pinfunction "1_1") (pintype "passive"))
      (node (ref "U24") (pin "1") (pinfunction "IN-_1") (pintype "input"))
    )
    (net (code "104") (name "Net-(U24B-IN+)") (class "Default")
      (node (ref "R233") (pin "2") (pinfunction "2_2") (pintype "passive"))
      (node (ref "R237") (pin "1") (pinfunction "1_1") (pintype "passive"))
      (node (ref "U24") (pin "6") (pinfunction "IN+_6") (pintype "input"))
    )
    (net (code "105") (name "Net-(U24B-IN-)") (class "Default")
      (node (ref "R253") (pin "1") (pinfunction "1_1") (pintype "passive"))
      (node (ref "R257") (pin "1") (pinfunction "1_1") (pintype "passive"))
      (node (ref "U24") (pin "7") (pinfunction "IN-_7") (pintype "input"))
    )
    (net (code "106") (name "Net-(U24C-IN+)") (class "Default")
      (node (ref "R234") (pin "2") (pinfunction "2_2") (pintype "passive"))
      (node (ref "R238") (pin "1") (pinfunction "1_1") (pintype "passive"))
      (node (ref "U24") (pin "10") (pinfunction "IN+_10") (pintype "input"))
    )
    (net (code "107") (name "Net-(U24C-IN-)") (class "Default")
      (node (ref "R254") (pin "1") (pinfunction "1_1") (pintype "passive"))
      (node (ref "R258") (pin "1") (pinfunction "1_1") (pintype "passive"))
      (node (ref "U24") (pin "9") (pinfunction "IN-_9") (pintype "input"))
    )
    (net (code "108") (name "Net-(U24D-IN+)") (class "Default")
      (node (ref "R235") (pin "2") (pinfunction "2_2") (pintype "passive"))
      (node (ref "R239") (pin "1") (pinfunction "1_1") (pintype "passive"))
      (node (ref "U24") (pin "14") (pinfunction "IN+_14") (pintype "input"))
    )
    (net (code "109") (name "Net-(U24D-IN-)") (class "Default")
      (node (ref "R255") (pin "1") (pinfunction "1_1") (pintype "passive"))
      (node (ref "R259") (pin "1") (pinfunction "1_1") (pintype "passive"))
      (node (ref "U24") (pin "15") (pinfunction "IN-_15") (pintype "input"))
    )
    (net (code "110") (name "Net-(U25A-IN+)") (class "Default")
      (node (ref "R264") (pin "2") (pinfunction "2_2") (pintype "passive"))
      (node (ref "R268") (pin "1") (pinfunction "1_1") (pintype "passive"))
      (node (ref "U25") (pin "2") (pinfunction "IN+_2") (pintype "input"))
    )
    (net (code "111") (name "Net-(U25A-IN-)") (class "Default")
      (node (ref "R284") (pin "1") (pinfunction "1_1") (pintype "passive"))
      (node (ref "R288") (pin "1") (pinfunction "1_1") (pintype "passive"))
      (node (ref "U25") (pin "1") (pinfunction "IN-_1") (pintype "input"))
    )
    (net (code "112") (name "Net-(U25B-IN+)") (class "Default")
      (node (ref "R265") (pin "2") (pinfunction "2_2") (pintype "passive"))
      (node (ref "R269") (pin "1") (pinfunction "1_1") (pintype "passive"))
      (node (ref "U25") (pin "6") (pinfunction "IN+_6") (pintype "input"))
    )
    (net (code "113") (name "Net-(U25B-IN-)") (class "Default")
      (node (ref "R285") (pin "1") (pinfunction "1_1") (pintype "passive"))
      (node (ref "R289") (pin "1") (pinfunction "1_1") (pintype "passive"))
      (node (ref "U25") (pin "7") (pinfunction "IN-_7") (pintype "input"))
    )
    (net (code "114") (name "Net-(U25C-IN+)") (class "Default")
      (node (ref "R266") (pin "2") (pinfunction "2_2") (pintype "passive"))
      (node (ref "R270") (pin "1") (pinfunction "1_1") (pintype "passive"))
      (node (ref "U25") (pin "10") (pinfunction "IN+_10") (pintype "input"))
    )
    (net (code "115") (name "Net-(U25C-IN-)") (class "Default")
      (node (ref "R286") (pin "1") (pinfunction "1_1") (pintype "passive"))
      (node (ref "R290") (pin "1") (pinfunction "1_1") (pintype "passive"))
      (node (ref "U25") (pin "9") (pinfunction "IN-_9") (pintype "input"))
    )
    (net (code "116") (name "Net-(U25D-IN+)") (class "Default")
      (node (ref "R267") (pin "2") (pinfunction "2_2") (pintype "passive"))
      (node (ref "R271") (pin "1") (pinfunction "1_1") (pintype "passive"))
      (node (ref "U25") (pin "14") (pinfunction "IN+_14") (pintype "input"))
    )
    (net (code "117") (name "Net-(U25D-IN-)") (class "Default")
      (node (ref "R287") (pin "1") (pinfunction "1_1") (pintype "passive"))
      (node (ref "R291") (pin "1") (pinfunction "1_1") (pintype "passive"))
      (node (ref "U25") (pin "15") (pinfunction "IN-_15") (pintype "input"))
    )
  )
)
